# Xibeca.net
KiCad netlist of a schematic drawn in EAGLE
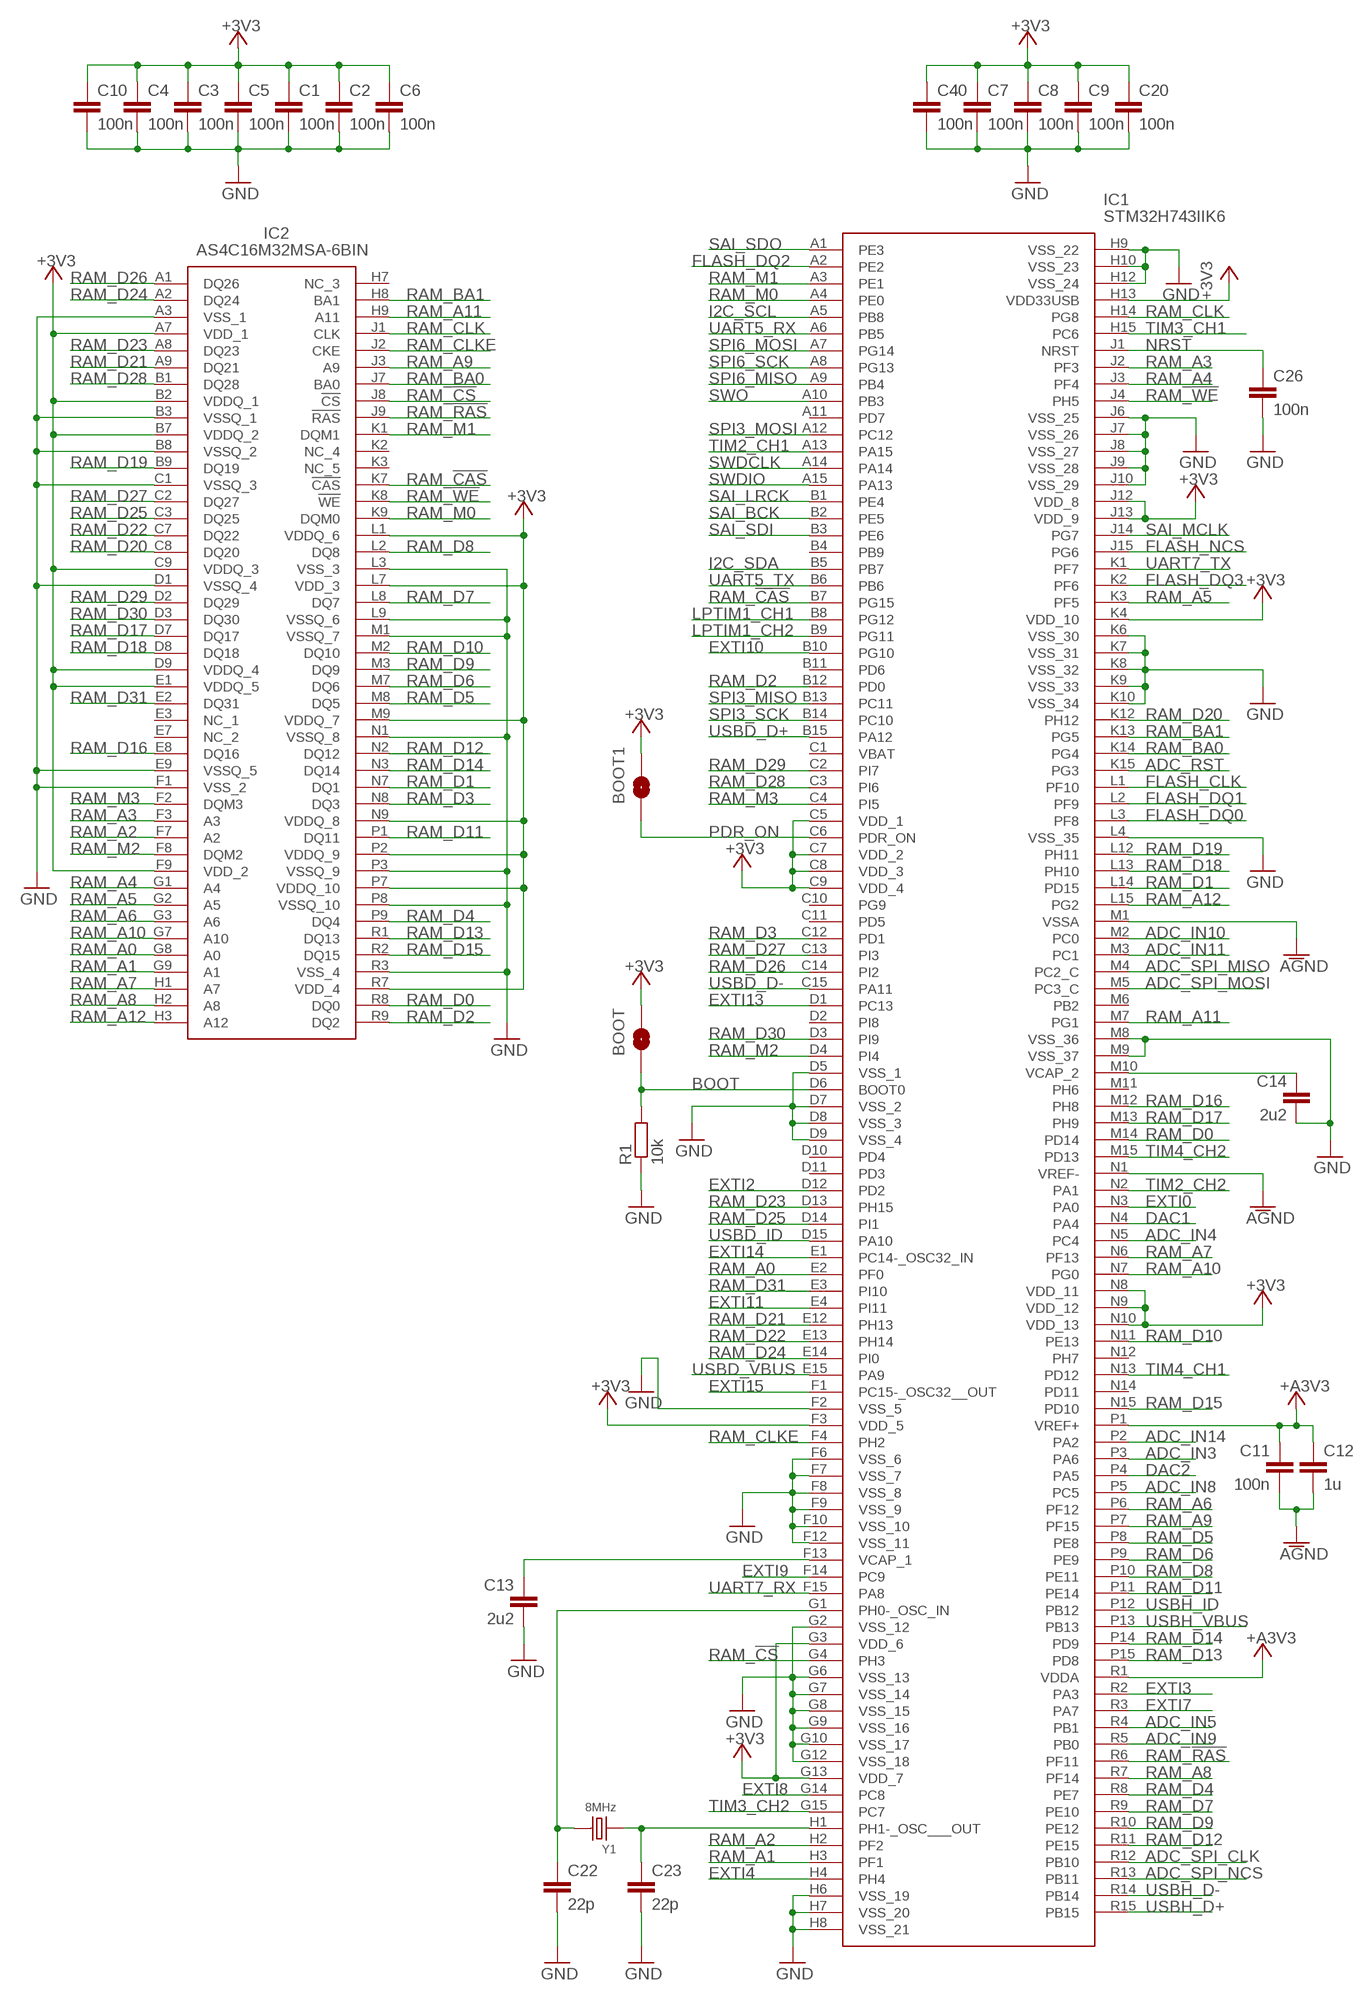
[diagram p0: schematic, sheet 1, part 1 of 2]
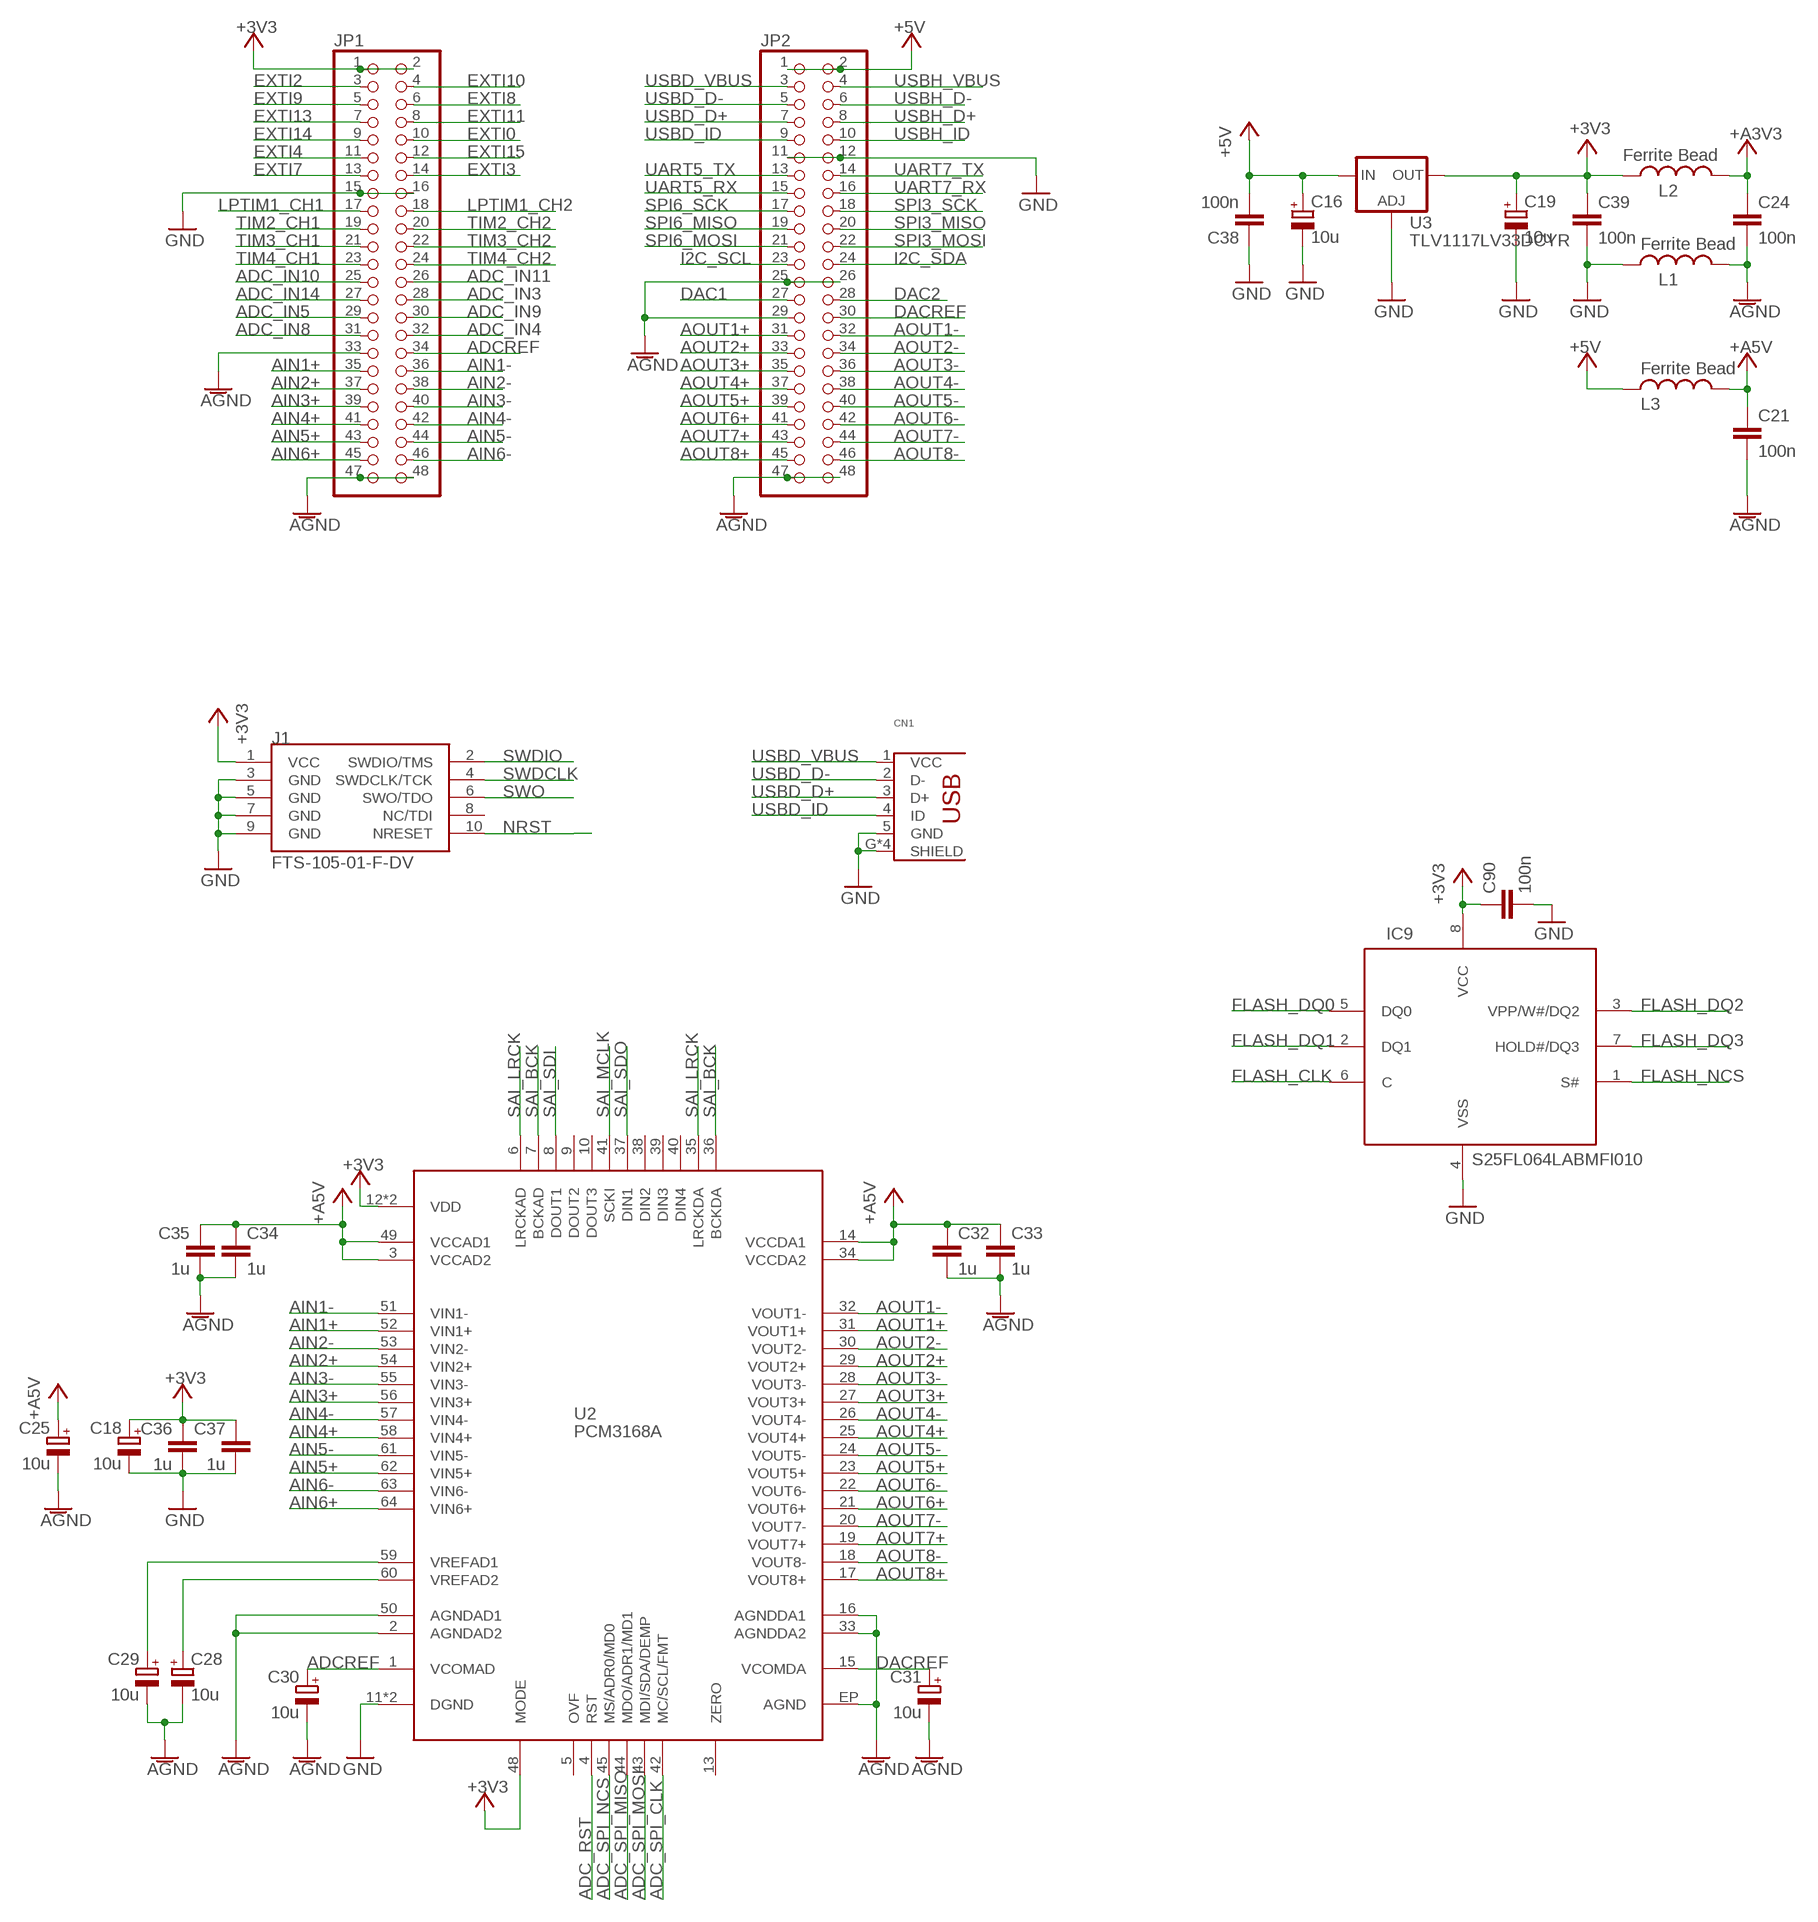
[diagram p1: schematic, sheet 1, part 2 of 2]

(export (version "E")
  (design (tool "Eeschema 10.0.6"))
  (components
    (comp (ref "BOOT")
      (value "SOLDERJUMPERNO")
      (footprint "eagle-import:SJ_2S-NO")
      (libsource (lib "eagle-import") (part "SOLDERJUMPERNO"))
    )
    (comp (ref "BOOT1")
      (value "SOLDERJUMPERNO")
      (footprint "eagle-import:SJ_2S-NO")
      (libsource (lib "eagle-import") (part "SOLDERJUMPERNO"))
    )
    (comp (ref "C1")
      (value "100n")
      (footprint "eagle-import:C0402")
      (libsource (lib "eagle-import") (part "C-EUC0402"))
    )
    (comp (ref "C2")
      (value "100n")
      (footprint "eagle-import:C0402")
      (libsource (lib "eagle-import") (part "C-EUC0402"))
    )
    (comp (ref "C3")
      (value "100n")
      (footprint "eagle-import:C0402")
      (libsource (lib "eagle-import") (part "C-EUC0402"))
    )
    (comp (ref "C4")
      (value "100n")
      (footprint "eagle-import:C0402")
      (libsource (lib "eagle-import") (part "C-EUC0402"))
    )
    (comp (ref "C5")
      (value "100n")
      (footprint "eagle-import:C0402")
      (libsource (lib "eagle-import") (part "C-EUC0402"))
    )
    (comp (ref "C6")
      (value "100n")
      (footprint "eagle-import:C0402")
      (libsource (lib "eagle-import") (part "C-EUC0402"))
    )
    (comp (ref "C7")
      (value "100n")
      (footprint "eagle-import:C0402")
      (libsource (lib "eagle-import") (part "C-EUC0402"))
    )
    (comp (ref "C8")
      (value "100n")
      (footprint "eagle-import:C0402")
      (libsource (lib "eagle-import") (part "C-EUC0402"))
    )
    (comp (ref "C9")
      (value "100n")
      (footprint "eagle-import:C0402")
      (libsource (lib "eagle-import") (part "C-EUC0402"))
    )
    (comp (ref "C10")
      (value "100n")
      (footprint "eagle-import:C0402")
      (libsource (lib "eagle-import") (part "C-EUC0402"))
    )
    (comp (ref "C11")
      (value "100n")
      (footprint "eagle-import:C0402")
      (libsource (lib "eagle-import") (part "C-EUC0402"))
    )
    (comp (ref "C12")
      (value "1u")
      (footprint "eagle-import:C0603")
      (libsource (lib "eagle-import") (part "C-EUC0603"))
    )
    (comp (ref "C13")
      (value "2u2")
      (footprint "eagle-import:C0402")
      (libsource (lib "eagle-import") (part "C-EUC0402"))
    )
    (comp (ref "C14")
      (value "2u2")
      (footprint "eagle-import:C0402")
      (libsource (lib "eagle-import") (part "C-EUC0402"))
    )
    (comp (ref "C16")
      (value "10u")
      (footprint "eagle-import:UD-4X5,8_NICHICON")
      (libsource (lib "eagle-import") (part "CPOL-EUUD-4X5,8"))
    )
    (comp (ref "C18")
      (value "10u")
      (footprint "eagle-import:UD-4X5,8_NICHICON")
      (libsource (lib "eagle-import") (part "CPOL-EUUD-4X5,8"))
    )
    (comp (ref "C19")
      (value "10u")
      (footprint "eagle-import:UD-4X5,8_NICHICON")
      (libsource (lib "eagle-import") (part "CPOL-EUUD-4X5,8"))
    )
    (comp (ref "C20")
      (value "100n")
      (footprint "eagle-import:C0402")
      (libsource (lib "eagle-import") (part "C-EUC0402"))
    )
    (comp (ref "C21")
      (value "100n")
      (footprint "eagle-import:C0402")
      (libsource (lib "eagle-import") (part "C-EUC0402"))
    )
    (comp (ref "C22")
      (value "22p")
      (footprint "eagle-import:C0402")
      (libsource (lib "eagle-import") (part "C-EUC0402"))
    )
    (comp (ref "C23")
      (value "22p")
      (footprint "eagle-import:C0402")
      (libsource (lib "eagle-import") (part "C-EUC0402"))
    )
    (comp (ref "C24")
      (value "100n")
      (footprint "eagle-import:C0402")
      (libsource (lib "eagle-import") (part "C-EUC0402"))
    )
    (comp (ref "C25")
      (value "10u")
      (footprint "eagle-import:UD-4X5,8_NICHICON")
      (libsource (lib "eagle-import") (part "CPOL-EUUD-4X5,8"))
    )
    (comp (ref "C26")
      (value "100n")
      (footprint "eagle-import:C0402")
      (libsource (lib "eagle-import") (part "C-EUC0402"))
    )
    (comp (ref "C28")
      (value "10u")
      (footprint "eagle-import:UD-4X5,8_NICHICON")
      (libsource (lib "eagle-import") (part "CPOL-EUUD-4X5,8"))
    )
    (comp (ref "C29")
      (value "10u")
      (footprint "eagle-import:UD-4X5,8_NICHICON")
      (libsource (lib "eagle-import") (part "CPOL-EUUD-4X5,8"))
    )
    (comp (ref "C30")
      (value "10u")
      (footprint "eagle-import:UD-4X5,8_NICHICON")
      (libsource (lib "eagle-import") (part "CPOL-EUUD-4X5,8"))
    )
    (comp (ref "C31")
      (value "10u")
      (footprint "eagle-import:UD-4X5,8_NICHICON")
      (libsource (lib "eagle-import") (part "CPOL-EUUD-4X5,8"))
    )
    (comp (ref "C32")
      (value "1u")
      (footprint "eagle-import:C0603")
      (libsource (lib "eagle-import") (part "C-EUC0603"))
    )
    (comp (ref "C33")
      (value "1u")
      (footprint "eagle-import:C0603")
      (libsource (lib "eagle-import") (part "C-EUC0603"))
    )
    (comp (ref "C34")
      (value "1u")
      (footprint "eagle-import:C0603")
      (libsource (lib "eagle-import") (part "C-EUC0603"))
    )
    (comp (ref "C35")
      (value "1u")
      (footprint "eagle-import:C0603")
      (libsource (lib "eagle-import") (part "C-EUC0603"))
    )
    (comp (ref "C36")
      (value "1u")
      (footprint "eagle-import:C0603")
      (libsource (lib "eagle-import") (part "C-EUC0603"))
    )
    (comp (ref "C37")
      (value "1u")
      (footprint "eagle-import:C0603")
      (libsource (lib "eagle-import") (part "C-EUC0603"))
    )
    (comp (ref "C38")
      (value "100n")
      (footprint "eagle-import:C0402")
      (libsource (lib "eagle-import") (part "C-EUC0402"))
    )
    (comp (ref "C39")
      (value "100n")
      (footprint "eagle-import:C0402")
      (libsource (lib "eagle-import") (part "C-EUC0402"))
    )
    (comp (ref "C40")
      (value "100n")
      (footprint "eagle-import:C0402")
      (libsource (lib "eagle-import") (part "C-EUC0402"))
    )
    (comp (ref "C90")
      (value "100n")
      (footprint "eagle-import:C0402")
      (libsource (lib "eagle-import") (part "C-EUC0402"))
    )
    (comp (ref "CN1")
      (value "USB_HRS_ZX62-B-5PA(11)MICRO.B")
      (footprint "eagle-import:HRS_ZX62RD-AB-5P8")
      (libsource (lib "eagle-import") (part "USB_HRS_ZX62-B-5PA(11)MICRO.B"))
    )
    (comp (ref "IC1")
      (value "STM32H743IIK6")
      (footprint "eagle-import:BGA201C65P15X15_1000X1000X60")
      (fields (field (name "MOUSER_PART_NUMBER") "511-STM32H743IIK6"))
      (libsource (lib "eagle-import") (part "STM32H743IIK6"))
    )
    (comp (ref "IC2")
      (value "AS4C16M32MSA-6BIN")
      (footprint "eagle-import:BGA90C80P9X15_800X1300X100")
      (fields (field (name "MOUSER_PART_NUMBER") "913-AS4C16M32MSA6BIN"))
      (libsource (lib "eagle-import") (part "AS4C16M32MSA-6BIN"))
    )
    (comp (ref "IC9")
      (value "S25FL064LABMFI010")
      (footprint "eagle-import:SO8W")
      (libsource (lib "eagle-import") (part "N25Q128A13"))
    )
    (comp (ref "J1")
      (value "FTS-105-01-F-DV")
      (footprint "eagle-import:2X5_1.27MM_SMD")
      (libsource (lib "eagle-import") (part "ARM_10SMD"))
    )
    (comp (ref "JP1")
      (value "PINHD-2X24")
      (footprint "eagle-import:2X24")
      (libsource (lib "eagle-import") (part "PINHD-2X24"))
    )
    (comp (ref "JP2")
      (value "PINHD-2X24")
      (footprint "eagle-import:2X24")
      (libsource (lib "eagle-import") (part "PINHD-2X24"))
    )
    (comp (ref "L1")
      (value "Ferrite Bead")
      (footprint "eagle-import:0603")
      (libsource (lib "eagle-import") (part "INDUCTOR"))
    )
    (comp (ref "L2")
      (value "Ferrite Bead")
      (footprint "eagle-import:0603")
      (libsource (lib "eagle-import") (part "INDUCTOR"))
    )
    (comp (ref "L3")
      (value "Ferrite Bead")
      (footprint "eagle-import:0603")
      (libsource (lib "eagle-import") (part "INDUCTOR"))
    )
    (comp (ref "R1")
      (value "10k")
      (footprint "eagle-import:0603")
      (libsource (lib "eagle-import") (part "R-EU_0603"))
    )
    (comp (ref "U2")
      (value "PCM3168A")
      (footprint "eagle-import:PQFP64")
      (libsource (lib "eagle-import") (part "PCM3168A"))
    )
    (comp (ref "U3")
      (value "TLV1117LV33DCYR")
      (footprint "eagle-import:SOT223")
      (libsource (lib "eagle-import") (part "LD117A?S33TR"))
    )
    (comp (ref "Y1")
      (value "8MHz")
      (footprint "eagle-import:X2-SMD-5.0X3.2X1.3MM")
      (fields (field (name "MPN") "5032/2P"))
      (libsource (lib "eagle-import") (part "SMD-CRYSTAL-8MHZ-20PF-20PPM(2P-5.0X3.2MM)"))
    )
  )
  (nets
    (net (code "1") (name "+3V3") (class "Default")
      (node (ref "BOOT") (pin "1") (pinfunction "1_1") (pintype "passive"))
      (node (ref "BOOT1") (pin "1") (pinfunction "1_1") (pintype "passive"))
      (node (ref "C1") (pin "1") (pinfunction "1_1") (pintype "passive"))
      (node (ref "C10") (pin "1") (pinfunction "1_1") (pintype "passive"))
      (node (ref "C18") (pin "+") (pinfunction "+_+") (pintype "passive"))
      (node (ref "C19") (pin "+") (pinfunction "+_+") (pintype "passive"))
      (node (ref "C2") (pin "1") (pinfunction "1_1") (pintype "passive"))
      (node (ref "C20") (pin "1") (pinfunction "1_1") (pintype "passive"))
      (node (ref "C3") (pin "1") (pinfunction "1_1") (pintype "passive"))
      (node (ref "C36") (pin "1") (pinfunction "1_1") (pintype "passive"))
      (node (ref "C37") (pin "1") (pinfunction "1_1") (pintype "passive"))
      (node (ref "C39") (pin "1") (pinfunction "1_1") (pintype "passive"))
      (node (ref "C4") (pin "1") (pinfunction "1_1") (pintype "passive"))
      (node (ref "C40") (pin "1") (pinfunction "1_1") (pintype "passive"))
      (node (ref "C5") (pin "1") (pinfunction "1_1") (pintype "passive"))
      (node (ref "C6") (pin "1") (pinfunction "1_1") (pintype "passive"))
      (node (ref "C7") (pin "1") (pinfunction "1_1") (pintype "passive"))
      (node (ref "C8") (pin "1") (pinfunction "1_1") (pintype "passive"))
      (node (ref "C9") (pin "1") (pinfunction "1_1") (pintype "passive"))
      (node (ref "C90") (pin "1") (pinfunction "1_1") (pintype "passive"))
      (node (ref "IC1") (pin "C5") (pinfunction "VDD_1_C5") (pintype "bidirectional"))
      (node (ref "IC1") (pin "C7") (pinfunction "VDD_2_C7") (pintype "bidirectional"))
      (node (ref "IC1") (pin "C8") (pinfunction "VDD_3_C8") (pintype "bidirectional"))
      (node (ref "IC1") (pin "C9") (pinfunction "VDD_4_C9") (pintype "bidirectional"))
      (node (ref "IC1") (pin "F3") (pinfunction "VDD_5_F3") (pintype "bidirectional"))
      (node (ref "IC1") (pin "G13") (pinfunction "VDD_7_G13") (pintype "bidirectional"))
      (node (ref "IC1") (pin "G3") (pinfunction "VDD_6_G3") (pintype "bidirectional"))
      (node (ref "IC1") (pin "H13") (pinfunction "VDD33USB_H13") (pintype "bidirectional"))
      (node (ref "IC1") (pin "J12") (pinfunction "VDD_8_J12") (pintype "bidirectional"))
      (node (ref "IC1") (pin "J13") (pinfunction "VDD_9_J13") (pintype "bidirectional"))
      (node (ref "IC1") (pin "K4") (pinfunction "VDD_10_K4") (pintype "bidirectional"))
      (node (ref "IC1") (pin "N10") (pinfunction "VDD_13_N10") (pintype "bidirectional"))
      (node (ref "IC1") (pin "N8") (pinfunction "VDD_11_N8") (pintype "bidirectional"))
      (node (ref "IC1") (pin "N9") (pinfunction "VDD_12_N9") (pintype "bidirectional"))
      (node (ref "IC2") (pin "A7") (pinfunction "VDD_1_A7") (pintype "bidirectional"))
      (node (ref "IC2") (pin "B2") (pinfunction "VDDQ_1_B2") (pintype "bidirectional"))
      (node (ref "IC2") (pin "B7") (pinfunction "VDDQ_2_B7") (pintype "bidirectional"))
      (node (ref "IC2") (pin "C9") (pinfunction "VDDQ_3_C9") (pintype "bidirectional"))
      (node (ref "IC2") (pin "D9") (pinfunction "VDDQ_4_D9") (pintype "bidirectional"))
      (node (ref "IC2") (pin "E1") (pinfunction "VDDQ_5_E1") (pintype "bidirectional"))
      (node (ref "IC2") (pin "F9") (pinfunction "VDD_2_F9") (pintype "bidirectional"))
      (node (ref "IC2") (pin "L1") (pinfunction "VDDQ_6_L1") (pintype "bidirectional"))
      (node (ref "IC2") (pin "L7") (pinfunction "VDD_3_L7") (pintype "bidirectional"))
      (node (ref "IC2") (pin "M9") (pinfunction "VDDQ_7_M9") (pintype "bidirectional"))
      (node (ref "IC2") (pin "N9") (pinfunction "VDDQ_8_N9") (pintype "bidirectional"))
      (node (ref "IC2") (pin "P2") (pinfunction "VDDQ_9_P2") (pintype "bidirectional"))
      (node (ref "IC2") (pin "P7") (pinfunction "VDDQ_10_P7") (pintype "bidirectional"))
      (node (ref "IC2") (pin "R7") (pinfunction "VDD_4_R7") (pintype "bidirectional"))
      (node (ref "IC9") (pin "8") (pinfunction "VCC_8") (pintype "bidirectional"))
      (node (ref "J1") (pin "1") (pinfunction "VCC_1") (pintype "bidirectional"))
      (node (ref "JP1") (pin "1") (pinfunction "1_1") (pintype "passive"))
      (node (ref "JP1") (pin "2") (pinfunction "2_2") (pintype "passive"))
      (node (ref "L2") (pin "2") (pinfunction "2_2") (pintype "passive"))
      (node (ref "U2") (pin "12") (pinfunction "VDD_12") (pintype "bidirectional"))
      (node (ref "U2") (pin "46") (pinfunction "VDD_46") (pintype "bidirectional"))
      (node (ref "U2") (pin "48") (pinfunction "MODE_48") (pintype "bidirectional"))
      (node (ref "U3") (pin "4") (pinfunction "OUT_4") (pintype "passive"))
    )
    (net (code "2") (name "+5V") (class "Default")
      (node (ref "C16") (pin "+") (pinfunction "+_+") (pintype "passive"))
      (node (ref "C38") (pin "2") (pinfunction "2_2") (pintype "passive"))
      (node (ref "JP2") (pin "1") (pinfunction "1_1") (pintype "passive"))
      (node (ref "JP2") (pin "2") (pinfunction "2_2") (pintype "passive"))
      (node (ref "L3") (pin "2") (pinfunction "2_2") (pintype "passive"))
      (node (ref "U3") (pin "3") (pinfunction "IN_3") (pintype "input"))
    )
    (net (code "3") (name "+A3V3") (class "Default")
      (node (ref "C11") (pin "1") (pinfunction "1_1") (pintype "passive"))
      (node (ref "C12") (pin "1") (pinfunction "1_1") (pintype "passive"))
      (node (ref "C24") (pin "1") (pinfunction "1_1") (pintype "passive"))
      (node (ref "IC1") (pin "P1") (pinfunction "VREF+_P1") (pintype "bidirectional"))
      (node (ref "IC1") (pin "R1") (pinfunction "VDDA_R1") (pintype "bidirectional"))
      (node (ref "L2") (pin "1") (pinfunction "1_1") (pintype "passive"))
    )
    (net (code "4") (name "+A5V") (class "Default")
      (node (ref "C21") (pin "1") (pinfunction "1_1") (pintype "passive"))
      (node (ref "C25") (pin "+") (pinfunction "+_+") (pintype "passive"))
      (node (ref "C32") (pin "1") (pinfunction "1_1") (pintype "passive"))
      (node (ref "C33") (pin "1") (pinfunction "1_1") (pintype "passive"))
      (node (ref "C34") (pin "1") (pinfunction "1_1") (pintype "passive"))
      (node (ref "C35") (pin "1") (pinfunction "1_1") (pintype "passive"))
      (node (ref "L3") (pin "1") (pinfunction "1_1") (pintype "passive"))
      (node (ref "U2") (pin "14") (pinfunction "VCCDA1_14") (pintype "bidirectional"))
      (node (ref "U2") (pin "3") (pinfunction "VCCAD2_3") (pintype "bidirectional"))
      (node (ref "U2") (pin "34") (pinfunction "VCCDA2_34") (pintype "bidirectional"))
      (node (ref "U2") (pin "49") (pinfunction "VCCAD1_49") (pintype "bidirectional"))
    )
    (net (code "5") (name "/ADCREF") (class "Default")
      (node (ref "C30") (pin "+") (pinfunction "+_+") (pintype "passive"))
      (node (ref "JP1") (pin "34") (pinfunction "34_34") (pintype "passive"))
      (node (ref "U2") (pin "1") (pinfunction "VCOMAD_1") (pintype "bidirectional"))
    )
    (net (code "6") (name "/ADC_IN3") (class "Default")
      (node (ref "IC1") (pin "P3") (pinfunction "PA6_P3") (pintype "bidirectional"))
      (node (ref "JP1") (pin "28") (pinfunction "28_28") (pintype "passive"))
    )
    (net (code "7") (name "/ADC_IN4") (class "Default")
      (node (ref "IC1") (pin "N5") (pinfunction "PC4_N5") (pintype "bidirectional"))
      (node (ref "JP1") (pin "32") (pinfunction "32_32") (pintype "passive"))
    )
    (net (code "8") (name "/ADC_IN5") (class "Default")
      (node (ref "IC1") (pin "R4") (pinfunction "PB1_R4") (pintype "bidirectional"))
      (node (ref "JP1") (pin "29") (pinfunction "29_29") (pintype "passive"))
    )
    (net (code "9") (name "/ADC_IN8") (class "Default")
      (node (ref "IC1") (pin "P5") (pinfunction "PC5_P5") (pintype "bidirectional"))
      (node (ref "JP1") (pin "31") (pinfunction "31_31") (pintype "passive"))
    )
    (net (code "10") (name "/ADC_IN9") (class "Default")
      (node (ref "IC1") (pin "R5") (pinfunction "PB0_R5") (pintype "bidirectional"))
      (node (ref "JP1") (pin "30") (pinfunction "30_30") (pintype "passive"))
    )
    (net (code "11") (name "/ADC_IN10") (class "Default")
      (node (ref "IC1") (pin "M2") (pinfunction "PC0_M2") (pintype "bidirectional"))
      (node (ref "JP1") (pin "25") (pinfunction "25_25") (pintype "passive"))
    )
    (net (code "12") (name "/ADC_IN11") (class "Default")
      (node (ref "IC1") (pin "M3") (pinfunction "PC1_M3") (pintype "bidirectional"))
      (node (ref "JP1") (pin "26") (pinfunction "26_26") (pintype "passive"))
    )
    (net (code "13") (name "/ADC_IN14") (class "Default")
      (node (ref "IC1") (pin "P2") (pinfunction "PA2_P2") (pintype "bidirectional"))
      (node (ref "JP1") (pin "27") (pinfunction "27_27") (pintype "passive"))
    )
    (net (code "14") (name "/ADC_RST") (class "Default")
      (node (ref "IC1") (pin "K15") (pinfunction "PG3_K15") (pintype "bidirectional"))
      (node (ref "U2") (pin "4") (pinfunction "RST_4") (pintype "bidirectional"))
    )
    (net (code "15") (name "/ADC_SPI_CLK") (class "Default")
      (node (ref "IC1") (pin "R12") (pinfunction "PB10_R12") (pintype "bidirectional"))
      (node (ref "U2") (pin "42") (pinfunction "MC/SCL/FMT_42") (pintype "bidirectional"))
    )
    (net (code "16") (name "/ADC_SPI_MISO") (class "Default")
      (node (ref "IC1") (pin "M4") (pinfunction "PC2_C_M4") (pintype "bidirectional"))
      (node (ref "U2") (pin "44") (pinfunction "MDO/ADR1/MD1_44") (pintype "bidirectional"))
    )
    (net (code "17") (name "/ADC_SPI_MOSI") (class "Default")
      (node (ref "IC1") (pin "M5") (pinfunction "PC3_C_M5") (pintype "bidirectional"))
      (node (ref "U2") (pin "43") (pinfunction "MDI/SDA/DEMP_43") (pintype "bidirectional"))
    )
    (net (code "18") (name "/ADC_SPI_NCS") (class "Default")
      (node (ref "IC1") (pin "R13") (pinfunction "PB11_R13") (pintype "bidirectional"))
      (node (ref "U2") (pin "45") (pinfunction "MS/ADR0/MD0_45") (pintype "bidirectional"))
    )
    (net (code "19") (name "/AIN1+") (class "Default")
      (node (ref "JP1") (pin "35") (pinfunction "35_35") (pintype "passive"))
      (node (ref "U2") (pin "52") (pinfunction "VIN1+_52") (pintype "bidirectional"))
    )
    (net (code "20") (name "/AIN1-") (class "Default")
      (node (ref "JP1") (pin "36") (pinfunction "36_36") (pintype "passive"))
      (node (ref "U2") (pin "51") (pinfunction "VIN1-_51") (pintype "bidirectional"))
    )
    (net (code "21") (name "/AIN2+") (class "Default")
      (node (ref "JP1") (pin "37") (pinfunction "37_37") (pintype "passive"))
      (node (ref "U2") (pin "54") (pinfunction "VIN2+_54") (pintype "bidirectional"))
    )
    (net (code "22") (name "/AIN2-") (class "Default")
      (node (ref "JP1") (pin "38") (pinfunction "38_38") (pintype "passive"))
      (node (ref "U2") (pin "53") (pinfunction "VIN2-_53") (pintype "bidirectional"))
    )
    (net (code "23") (name "/AIN3+") (class "Default")
      (node (ref "JP1") (pin "39") (pinfunction "39_39") (pintype "passive"))
      (node (ref "U2") (pin "56") (pinfunction "VIN3+_56") (pintype "bidirectional"))
    )
    (net (code "24") (name "/AIN3-") (class "Default")
      (node (ref "JP1") (pin "40") (pinfunction "40_40") (pintype "passive"))
      (node (ref "U2") (pin "55") (pinfunction "VIN3-_55") (pintype "bidirectional"))
    )
    (net (code "25") (name "/AIN4+") (class "Default")
      (node (ref "JP1") (pin "41") (pinfunction "41_41") (pintype "passive"))
      (node (ref "U2") (pin "58") (pinfunction "VIN4+_58") (pintype "bidirectional"))
    )
    (net (code "26") (name "/AIN4-") (class "Default")
      (node (ref "JP1") (pin "42") (pinfunction "42_42") (pintype "passive"))
      (node (ref "U2") (pin "57") (pinfunction "VIN4-_57") (pintype "bidirectional"))
    )
    (net (code "27") (name "/AIN5+") (class "Default")
      (node (ref "JP1") (pin "43") (pinfunction "43_43") (pintype "passive"))
      (node (ref "U2") (pin "62") (pinfunction "VIN5+_62") (pintype "bidirectional"))
    )
    (net (code "28") (name "/AIN5-") (class "Default")
      (node (ref "JP1") (pin "44") (pinfunction "44_44") (pintype "passive"))
      (node (ref "U2") (pin "61") (pinfunction "VIN5-_61") (pintype "bidirectional"))
    )
    (net (code "29") (name "/AIN6+") (class "Default")
      (node (ref "JP1") (pin "45") (pinfunction "45_45") (pintype "passive"))
      (node (ref "U2") (pin "64") (pinfunction "VIN6+_64") (pintype "bidirectional"))
    )
    (net (code "30") (name "/AIN6-") (class "Default")
      (node (ref "JP1") (pin "46") (pinfunction "46_46") (pintype "passive"))
      (node (ref "U2") (pin "63") (pinfunction "VIN6-_63") (pintype "bidirectional"))
    )
    (net (code "31") (name "/AOUT1+") (class "Default")
      (node (ref "JP2") (pin "31") (pinfunction "31_31") (pintype "passive"))
      (node (ref "U2") (pin "31") (pinfunction "VOUT1+_31") (pintype "bidirectional"))
    )
    (net (code "32") (name "/AOUT1-") (class "Default")
      (node (ref "JP2") (pin "32") (pinfunction "32_32") (pintype "passive"))
      (node (ref "U2") (pin "32") (pinfunction "VOUT1-_32") (pintype "bidirectional"))
    )
    (net (code "33") (name "/AOUT2+") (class "Default")
      (node (ref "JP2") (pin "33") (pinfunction "33_33") (pintype "passive"))
      (node (ref "U2") (pin "29") (pinfunction "VOUT2+_29") (pintype "bidirectional"))
    )
    (net (code "34") (name "/AOUT2-") (class "Default")
      (node (ref "JP2") (pin "34") (pinfunction "34_34") (pintype "passive"))
      (node (ref "U2") (pin "30") (pinfunction "VOUT2-_30") (pintype "bidirectional"))
    )
    (net (code "35") (name "/AOUT3+") (class "Default")
      (node (ref "JP2") (pin "35") (pinfunction "35_35") (pintype "passive"))
      (node (ref "U2") (pin "27") (pinfunction "VOUT3+_27") (pintype "bidirectional"))
    )
    (net (code "36") (name "/AOUT3-") (class "Default")
      (node (ref "JP2") (pin "36") (pinfunction "36_36") (pintype "passive"))
      (node (ref "U2") (pin "28") (pinfunction "VOUT3-_28") (pintype "bidirectional"))
    )
    (net (code "37") (name "/AOUT4+") (class "Default")
      (node (ref "JP2") (pin "37") (pinfunction "37_37") (pintype "passive"))
      (node (ref "U2") (pin "25") (pinfunction "VOUT4+_25") (pintype "bidirectional"))
    )
    (net (code "38") (name "/AOUT4-") (class "Default")
      (node (ref "JP2") (pin "38") (pinfunction "38_38") (pintype "passive"))
      (node (ref "U2") (pin "26") (pinfunction "VOUT4-_26") (pintype "bidirectional"))
    )
    (net (code "39") (name "/AOUT5+") (class "Default")
      (node (ref "JP2") (pin "39") (pinfunction "39_39") (pintype "passive"))
      (node (ref "U2") (pin "23") (pinfunction "VOUT5+_23") (pintype "bidirectional"))
    )
    (net (code "40") (name "/AOUT5-") (class "Default")
      (node (ref "JP2") (pin "40") (pinfunction "40_40") (pintype "passive"))
      (node (ref "U2") (pin "24") (pinfunction "VOUT5-_24") (pintype "bidirectional"))
    )
    (net (code "41") (name "/AOUT6+") (class "Default")
      (node (ref "JP2") (pin "41") (pinfunction "41_41") (pintype "passive"))
      (node (ref "U2") (pin "21") (pinfunction "VOUT6+_21") (pintype "bidirectional"))
    )
    (net (code "42") (name "/AOUT6-") (class "Default")
      (node (ref "JP2") (pin "42") (pinfunction "42_42") (pintype "passive"))
      (node (ref "U2") (pin "22") (pinfunction "VOUT6-_22") (pintype "bidirectional"))
    )
    (net (code "43") (name "/AOUT7+") (class "Default")
      (node (ref "JP2") (pin "43") (pinfunction "43_43") (pintype "passive"))
      (node (ref "U2") (pin "19") (pinfunction "VOUT7+_19") (pintype "bidirectional"))
    )
    (net (code "44") (name "/AOUT7-") (class "Default")
      (node (ref "JP2") (pin "44") (pinfunction "44_44") (pintype "passive"))
      (node (ref "U2") (pin "20") (pinfunction "VOUT7-_20") (pintype "bidirectional"))
    )
    (net (code "45") (name "/AOUT8+") (class "Default")
      (node (ref "JP2") (pin "45") (pinfunction "45_45") (pintype "passive"))
      (node (ref "U2") (pin "17") (pinfunction "VOUT8+_17") (pintype "bidirectional"))
    )
    (net (code "46") (name "/AOUT8-") (class "Default")
      (node (ref "JP2") (pin "46") (pinfunction "46_46") (pintype "passive"))
      (node (ref "U2") (pin "18") (pinfunction "VOUT8-_18") (pintype "bidirectional"))
    )
    (net (code "47") (name "/BOOT") (class "Default")
      (node (ref "BOOT") (pin "2") (pinfunction "2_2") (pintype "passive"))
      (node (ref "IC1") (pin "D6") (pinfunction "BOOT0_D6") (pintype "bidirectional"))
      (node (ref "R1") (pin "2") (pinfunction "2_2") (pintype "passive"))
    )
    (net (code "48") (name "/DAC1") (class "Default")
      (node (ref "IC1") (pin "N4") (pinfunction "PA4_N4") (pintype "bidirectional"))
      (node (ref "JP2") (pin "27") (pinfunction "27_27") (pintype "passive"))
    )
    (net (code "49") (name "/DAC2") (class "Default")
      (node (ref "IC1") (pin "P4") (pinfunction "PA5_P4") (pintype "bidirectional"))
      (node (ref "JP2") (pin "28") (pinfunction "28_28") (pintype "passive"))
    )
    (net (code "50") (name "/DACREF") (class "Default")
      (node (ref "C31") (pin "+") (pinfunction "+_+") (pintype "passive"))
      (node (ref "JP2") (pin "30") (pinfunction "30_30") (pintype "passive"))
      (node (ref "U2") (pin "15") (pinfunction "VCOMDA_15") (pintype "bidirectional"))
    )
    (net (code "51") (name "/EXTI0") (class "Default")
      (node (ref "IC1") (pin "N3") (pinfunction "PA0_N3") (pintype "bidirectional"))
      (node (ref "JP1") (pin "10") (pinfunction "10_10") (pintype "passive"))
    )
    (net (code "52") (name "/EXTI2") (class "Default")
      (node (ref "IC1") (pin "D12") (pinfunction "PD2_D12") (pintype "bidirectional"))
      (node (ref "JP1") (pin "3") (pinfunction "3_3") (pintype "passive"))
    )
    (net (code "53") (name "/EXTI3") (class "Default")
      (node (ref "IC1") (pin "R2") (pinfunction "PA3_R2") (pintype "bidirectional"))
      (node (ref "JP1") (pin "14") (pinfunction "14_14") (pintype "passive"))
    )
    (net (code "54") (name "/EXTI4") (class "Default")
      (node (ref "IC1") (pin "H4") (pinfunction "PH4_H4") (pintype "bidirectional"))
      (node (ref "JP1") (pin "11") (pinfunction "11_11") (pintype "passive"))
    )
    (net (code "55") (name "/EXTI7") (class "Default")
      (node (ref "IC1") (pin "R3") (pinfunction "PA7_R3") (pintype "bidirectional"))
      (node (ref "JP1") (pin "13") (pinfunction "13_13") (pintype "passive"))
    )
    (net (code "56") (name "/EXTI8") (class "Default")
      (node (ref "IC1") (pin "G14") (pinfunction "PC8_G14") (pintype "bidirectional"))
      (node (ref "JP1") (pin "6") (pinfunction "6_6") (pintype "passive"))
    )
    (net (code "57") (name "/EXTI9") (class "Default")
      (node (ref "IC1") (pin "F14") (pinfunction "PC9_F14") (pintype "bidirectional"))
      (node (ref "JP1") (pin "5") (pinfunction "5_5") (pintype "passive"))
    )
    (net (code "58") (name "/EXTI10") (class "Default")
      (node (ref "IC1") (pin "B10") (pinfunction "PG10_B10") (pintype "bidirectional"))
      (node (ref "JP1") (pin "4") (pinfunction "4_4") (pintype "passive"))
    )
    (net (code "59") (name "/EXTI11") (class "Default")
      (node (ref "IC1") (pin "E4") (pinfunction "PI11_E4") (pintype "bidirectional"))
      (node (ref "JP1") (pin "8") (pinfunction "8_8") (pintype "passive"))
    )
    (net (code "60") (name "/EXTI13") (class "Default")
      (node (ref "IC1") (pin "D1") (pinfunction "PC13_D1") (pintype "bidirectional"))
      (node (ref "JP1") (pin "7") (pinfunction "7_7") (pintype "passive"))
    )
    (net (code "61") (name "/EXTI14") (class "Default")
      (node (ref "IC1") (pin "E1") (pinfunction "PC14-_OSC32_IN_E1") (pintype "bidirectional"))
      (node (ref "JP1") (pin "9") (pinfunction "9_9") (pintype "passive"))
    )
    (net (code "62") (name "/EXTI15") (class "Default")
      (node (ref "IC1") (pin "F1") (pinfunction "PC15-_OSC32__OUT_F1") (pintype "bidirectional"))
      (node (ref "JP1") (pin "12") (pinfunction "12_12") (pintype "passive"))
    )
    (net (code "63") (name "/FLASH_CLK") (class "Default")
      (node (ref "IC1") (pin "L1") (pinfunction "PF10_L1") (pintype "bidirectional"))
      (node (ref "IC9") (pin "6") (pinfunction "C_6") (pintype "bidirectional"))
    )
    (net (code "64") (name "/FLASH_DQ0") (class "Default")
      (node (ref "IC1") (pin "L3") (pinfunction "PF8_L3") (pintype "bidirectional"))
      (node (ref "IC9") (pin "5") (pinfunction "DQ0_5") (pintype "bidirectional"))
    )
    (net (code "65") (name "/FLASH_DQ1") (class "Default")
      (node (ref "IC1") (pin "L2") (pinfunction "PF9_L2") (pintype "bidirectional"))
      (node (ref "IC9") (pin "2") (pinfunction "DQ1_2") (pintype "bidirectional"))
    )
    (net (code "66") (name "/FLASH_DQ2") (class "Default")
      (node (ref "IC1") (pin "A2") (pinfunction "PE2_A2") (pintype "bidirectional"))
      (node (ref "IC9") (pin "3") (pinfunction "VPP/W#/DQ2_3") (pintype "bidirectional"))
    )
    (net (code "67") (name "/FLASH_DQ3") (class "Default")
      (node (ref "IC1") (pin "K2") (pinfunction "PF6_K2") (pintype "bidirectional"))
      (node (ref "IC9") (pin "7") (pinfunction "HOLD#/DQ3_7") (pintype "bidirectional"))
    )
    (net (code "68") (name "/FLASH_NCS") (class "Default")
      (node (ref "IC1") (pin "J15") (pinfunction "PG6_J15") (pintype "bidirectional"))
      (node (ref "IC9") (pin "1") (pinfunction "S#_1") (pintype "bidirectional"))
    )
    (net (code "69") (name "/I2C_SCL") (class "Default")
      (node (ref "IC1") (pin "A5") (pinfunction "PB8_A5") (pintype "bidirectional"))
      (node (ref "JP2") (pin "23") (pinfunction "23_23") (pintype "passive"))
    )
    (net (code "70") (name "/I2C_SDA") (class "Default")
      (node (ref "IC1") (pin "B5") (pinfunction "PB7_B5") (pintype "bidirectional"))
      (node (ref "JP2") (pin "24") (pinfunction "24_24") (pintype "passive"))
    )
    (net (code "71") (name "/LPTIM1_CH1") (class "Default")
      (node (ref "IC1") (pin "B8") (pinfunction "PG12_B8") (pintype "bidirectional"))
      (node (ref "JP1") (pin "17") (pinfunction "17_17") (pintype "passive"))
    )
    (net (code "72") (name "/LPTIM1_CH2") (class "Default")
      (node (ref "IC1") (pin "B9") (pinfunction "PG11_B9") (pintype "bidirectional"))
      (node (ref "JP1") (pin "18") (pinfunction "18_18") (pintype "passive"))
    )
    (net (code "73") (name "/NRST") (class "Default")
      (node (ref "C26") (pin "1") (pinfunction "1_1") (pintype "passive"))
      (node (ref "IC1") (pin "J1") (pinfunction "NRST_J1") (pintype "bidirectional"))
      (node (ref "J1") (pin "10") (pinfunction "NRESET_10") (pintype "bidirectional"))
    )
    (net (code "74") (name "/PDR_ON") (class "Default")
      (node (ref "BOOT1") (pin "2") (pinfunction "2_2") (pintype "passive"))
      (node (ref "IC1") (pin "C6") (pinfunction "PDR_ON_C6") (pintype "bidirectional"))
    )
    (net (code "75") (name "/RAM_A0") (class "Default")
      (node (ref "IC1") (pin "E2") (pinfunction "PF0_E2") (pintype "bidirectional"))
      (node (ref "IC2") (pin "G8") (pinfunction "A0_G8") (pintype "bidirectional"))
    )
    (net (code "76") (name "/RAM_A1") (class "Default")
      (node (ref "IC1") (pin "H3") (pinfunction "PF1_H3") (pintype "bidirectional"))
      (node (ref "IC2") (pin "G9") (pinfunction "A1_G9") (pintype "bidirectional"))
    )
    (net (code "77") (name "/RAM_A2") (class "Default")
      (node (ref "IC1") (pin "H2") (pinfunction "PF2_H2") (pintype "bidirectional"))
      (node (ref "IC2") (pin "F7") (pinfunction "A2_F7") (pintype "bidirectional"))
    )
    (net (code "78") (name "/RAM_A3") (class "Default")
      (node (ref "IC1") (pin "J2") (pinfunction "PF3_J2") (pintype "bidirectional"))
      (node (ref "IC2") (pin "F3") (pinfunction "A3_F3") (pintype "bidirectional"))
    )
    (net (code "79") (name "/RAM_A4") (class "Default")
      (node (ref "IC1") (pin "J3") (pinfunction "PF4_J3") (pintype "bidirectional"))
      (node (ref "IC2") (pin "G1") (pinfunction "A4_G1") (pintype "bidirectional"))
    )
    (net (code "80") (name "/RAM_A5") (class "Default")
      (node (ref "IC1") (pin "K3") (pinfunction "PF5_K3") (pintype "bidirectional"))
      (node (ref "IC2") (pin "G2") (pinfunction "A5_G2") (pintype "bidirectional"))
    )
    (net (code "81") (name "/RAM_A6") (class "Default")
      (node (ref "IC1") (pin "P6") (pinfunction "PF12_P6") (pintype "bidirectional"))
      (node (ref "IC2") (pin "G3") (pinfunction "A6_G3") (pintype "bidirectional"))
    )
    (net (code "82") (name "/RAM_A7") (class "Default")
      (node (ref "IC1") (pin "N6") (pinfunction "PF13_N6") (pintype "bidirectional"))
      (node (ref "IC2") (pin "H1") (pinfunction "A7_H1") (pintype "bidirectional"))
    )
    (net (code "83") (name "/RAM_A8") (class "Default")
      (node (ref "IC1") (pin "R7") (pinfunction "PF14_R7") (pintype "bidirectional"))
      (node (ref "IC2") (pin "H2") (pinfunction "A8_H2") (pintype "bidirectional"))
    )
    (net (code "84") (name "/RAM_A9") (class "Default")
      (node (ref "IC1") (pin "P7") (pinfunction "PF15_P7") (pintype "bidirectional"))
      (node (ref "IC2") (pin "J3") (pinfunction "A9_J3") (pintype "bidirectional"))
    )
    (net (code "85") (name "/RAM_A10") (class "Default")
      (node (ref "IC1") (pin "N7") (pinfunction "PG0_N7") (pintype "bidirectional"))
      (node (ref "IC2") (pin "G7") (pinfunction "A10_G7") (pintype "bidirectional"))
    )
    (net (code "86") (name "/RAM_A11") (class "Default")
      (node (ref "IC1") (pin "M7") (pinfunction "PG1_M7") (pintype "bidirectional"))
      (node (ref "IC2") (pin "H9") (pinfunction "A11_H9") (pintype "bidirectional"))
    )
    (net (code "87") (name "/RAM_A12") (class "Default")
      (node (ref "IC1") (pin "L15") (pinfunction "PG2_L15") (pintype "bidirectional"))
      (node (ref "IC2") (pin "H3") (pinfunction "A12_H3") (pintype "bidirectional"))
    )
    (net (code "88") (name "/RAM_BA0") (class "Default")
      (node (ref "IC1") (pin "K14") (pinfunction "PG4_K14") (pintype "bidirectional"))
      (node (ref "IC2") (pin "J7") (pinfunction "BA0_J7") (pintype "bidirectional"))
    )
    (net (code "89") (name "/RAM_BA1") (class "Default")
      (node (ref "IC1") (pin "K13") (pinfunction "PG5_K13") (pintype "bidirectional"))
      (node (ref "IC2") (pin "H8") (pinfunction "BA1_H8") (pintype "bidirectional"))
    )
    (net (code "90") (name "/RAM_CLK") (class "Default")
      (node (ref "IC1") (pin "H14") (pinfunction "PG8_H14") (pintype "bidirectional"))
      (node (ref "IC2") (pin "J1") (pinfunction "CLK_J1") (pintype "bidirectional"))
    )
    (net (code "91") (name "/RAM_CLKE") (class "Default")
      (node (ref "IC1") (pin "F4") (pinfunction "PH2_F4") (pintype "bidirectional"))
      (node (ref "IC2") (pin "J2") (pinfunction "CKE_J2") (pintype "bidirectional"))
    )
    (net (code "92") (name "/RAM_D0") (class "Default")
      (node (ref "IC1") (pin "M14") (pinfunction "PD14_M14") (pintype "bidirectional"))
      (node (ref "IC2") (pin "R8") (pinfunction "DQ0_R8") (pintype "bidirectional"))
    )
    (net (code "93") (name "/RAM_D1") (class "Default")
      (node (ref "IC1") (pin "L14") (pinfunction "PD15_L14") (pintype "bidirectional"))
      (node (ref "IC2") (pin "N7") (pinfunction "DQ1_N7") (pintype "bidirectional"))
    )
    (net (code "94") (name "/RAM_D2") (class "Default")
      (node (ref "IC1") (pin "B12") (pinfunction "PD0_B12") (pintype "bidirectional"))
      (node (ref "IC2") (pin "R9") (pinfunction "DQ2_R9") (pintype "bidirectional"))
    )
    (net (code "95") (name "/RAM_D3") (class "Default")
      (node (ref "IC1") (pin "C12") (pinfunction "PD1_C12") (pintype "bidirectional"))
      (node (ref "IC2") (pin "N8") (pinfunction "DQ3_N8") (pintype "bidirectional"))
    )
    (net (code "96") (name "/RAM_D4") (class "Default")
      (node (ref "IC1") (pin "R8") (pinfunction "PE7_R8") (pintype "bidirectional"))
      (node (ref "IC2") (pin "P9") (pinfunction "DQ4_P9") (pintype "bidirectional"))
    )
    (net (code "97") (name "/RAM_D5") (class "Default")
      (node (ref "IC1") (pin "P8") (pinfunction "PE8_P8") (pintype "bidirectional"))
      (node (ref "IC2") (pin "M8") (pinfunction "DQ5_M8") (pintype "bidirectional"))
    )
    (net (code "98") (name "/RAM_D6") (class "Default")
      (node (ref "IC1") (pin "P9") (pinfunction "PE9_P9") (pintype "bidirectional"))
      (node (ref "IC2") (pin "M7") (pinfunction "DQ6_M7") (pintype "bidirectional"))
    )
    (net (code "99") (name "/RAM_D7") (class "Default")
      (node (ref "IC1") (pin "R9") (pinfunction "PE10_R9") (pintype "bidirectional"))
      (node (ref "IC2") (pin "L8") (pinfunction "DQ7_L8") (pintype "bidirectional"))
    )
    (net (code "100") (name "/RAM_D8") (class "Default")
      (node (ref "IC1") (pin "P10") (pinfunction "PE11_P10") (pintype "bidirectional"))
      (node (ref "IC2") (pin "L2") (pinfunction "DQ8_L2") (pintype "bidirectional"))
    )
    (net (code "101") (name "/RAM_D9") (class "Default")
      (node (ref "IC1") (pin "R10") (pinfunction "PE12_R10") (pintype "bidirectional"))
      (node (ref "IC2") (pin "M3") (pinfunction "DQ9_M3") (pintype "bidirectional"))
    )
    (net (code "102") (name "/RAM_D10") (class "Default")
      (node (ref "IC1") (pin "N11") (pinfunction "PE13_N11") (pintype "bidirectional"))
      (node (ref "IC2") (pin "M2") (pinfunction "DQ10_M2") (pintype "bidirectional"))
    )
    (net (code "103") (name "/RAM_D11") (class "Default")
      (node (ref "IC1") (pin "P11") (pinfunction "PE14_P11") (pintype "bidirectional"))
      (node (ref "IC2") (pin "P1") (pinfunction "DQ11_P1") (pintype "bidirectional"))
    )
    (net (code "104") (name "/RAM_D12") (class "Default")
      (node (ref "IC1") (pin "R11") (pinfunction "PE15_R11") (pintype "bidirectional"))
      (node (ref "IC2") (pin "N2") (pinfunction "DQ12_N2") (pintype "bidirectional"))
    )
    (net (code "105") (name "/RAM_D13") (class "Default")
      (node (ref "IC1") (pin "P15") (pinfunction "PD8_P15") (pintype "bidirectional"))
      (node (ref "IC2") (pin "R1") (pinfunction "DQ13_R1") (pintype "bidirectional"))
    )
    (net (code "106") (name "/RAM_D14") (class "Default")
      (node (ref "IC1") (pin "P14") (pinfunction "PD9_P14") (pintype "bidirectional"))
      (node (ref "IC2") (pin "N3") (pinfunction "DQ14_N3") (pintype "bidirectional"))
    )
    (net (code "107") (name "/RAM_D15") (class "Default")
      (node (ref "IC1") (pin "N15") (pinfunction "PD10_N15") (pintype "bidirectional"))
      (node (ref "IC2") (pin "R2") (pinfunction "DQ15_R2") (pintype "bidirectional"))
    )
    (net (code "108") (name "/RAM_D16") (class "Default")
      (node (ref "IC1") (pin "M12") (pinfunction "PH8_M12") (pintype "bidirectional"))
      (node (ref "IC2") (pin "E8") (pinfunction "DQ16_E8") (pintype "bidirectional"))
    )
    (net (code "109") (name "/RAM_D17") (class "Default")
      (node (ref "IC1") (pin "M13") (pinfunction "PH9_M13") (pintype "bidirectional"))
      (node (ref "IC2") (pin "D7") (pinfunction "DQ17_D7") (pintype "bidirectional"))
    )
    (net (code "110") (name "/RAM_D18") (class "Default")
      (node (ref "IC1") (pin "L13") (pinfunction "PH10_L13") (pintype "bidirectional"))
      (node (ref "IC2") (pin "D8") (pinfunction "DQ18_D8") (pintype "bidirectional"))
    )
    (net (code "111") (name "/RAM_D19") (class "Default")
      (node (ref "IC1") (pin "L12") (pinfunction "PH11_L12") (pintype "bidirectional"))
      (node (ref "IC2") (pin "B9") (pinfunction "DQ19_B9") (pintype "bidirectional"))
    )
    (net (code "112") (name "/RAM_D20") (class "Default")
      (node (ref "IC1") (pin "K12") (pinfunction "PH12_K12") (pintype "bidirectional"))
      (node (ref "IC2") (pin "C8") (pinfunction "DQ20_C8") (pintype "bidirectional"))
    )
    (net (code "113") (name "/RAM_D21") (class "Default")
      (node (ref "IC1") (pin "E12") (pinfunction "PH13_E12") (pintype "bidirectional"))
      (node (ref "IC2") (pin "A9") (pinfunction "DQ21_A9") (pintype "bidirectional"))
    )
    (net (code "114") (name "/RAM_D22") (class "Default")
      (node (ref "IC1") (pin "E13") (pinfunction "PH14_E13") (pintype "bidirectional"))
      (node (ref "IC2") (pin "C7") (pinfunction "DQ22_C7") (pintype "bidirectional"))
    )
    (net (code "115") (name "/RAM_D23") (class "Default")
      (node (ref "IC1") (pin "D13") (pinfunction "PH15_D13") (pintype "bidirectional"))
      (node (ref "IC2") (pin "A8") (pinfunction "DQ23_A8") (pintype "bidirectional"))
    )
    (net (code "116") (name "/RAM_D24") (class "Default")
      (node (ref "IC1") (pin "E14") (pinfunction "PI0_E14") (pintype "bidirectional"))
      (node (ref "IC2") (pin "A2") (pinfunction "DQ24_A2") (pintype "bidirectional"))
    )
    (net (code "117") (name "/RAM_D25") (class "Default")
      (node (ref "IC1") (pin "D14") (pinfunction "PI1_D14") (pintype "bidirectional"))
      (node (ref "IC2") (pin "C3") (pinfunction "DQ25_C3") (pintype "bidirectional"))
    )
    (net (code "118") (name "/RAM_D26") (class "Default")
      (node (ref "IC1") (pin "C14") (pinfunction "PI2_C14") (pintype "bidirectional"))
      (node (ref "IC2") (pin "A1") (pinfunction "DQ26_A1") (pintype "bidirectional"))
    )
    (net (code "119") (name "/RAM_D27") (class "Default")
      (node (ref "IC1") (pin "C13") (pinfunction "PI3_C13") (pintype "bidirectional"))
      (node (ref "IC2") (pin "C2") (pinfunction "DQ27_C2") (pintype "bidirectional"))
    )
    (net (code "120") (name "/RAM_D28") (class "Default")
      (node (ref "IC1") (pin "C3") (pinfunction "PI6_C3") (pintype "bidirectional"))
      (node (ref "IC2") (pin "B1") (pinfunction "DQ28_B1") (pintype "bidirectional"))
    )
    (net (code "121") (name "/RAM_D29") (class "Default")
      (node (ref "IC1") (pin "C2") (pinfunction "PI7_C2") (pintype "bidirectional"))
      (node (ref "IC2") (pin "D2") (pinfunction "DQ29_D2") (pintype "bidirectional"))
    )
    (net (code "122") (name "/RAM_D30") (class "Default")
      (node (ref "IC1") (pin "D3") (pinfunction "PI9_D3") (pintype "bidirectional"))
      (node (ref "IC2") (pin "D3") (pinfunction "DQ30_D3") (pintype "bidirectional"))
    )
    (net (code "123") (name "/RAM_D31") (class "Default")
      (node (ref "IC1") (pin "E3") (pinfunction "PI10_E3") (pintype "bidirectional"))
      (node (ref "IC2") (pin "E2") (pinfunction "DQ31_E2") (pintype "bidirectional"))
    )
    (net (code "124") (name "/RAM_M0") (class "Default")
      (node (ref "IC1") (pin "A4") (pinfunction "PE0_A4") (pintype "bidirectional"))
      (node (ref "IC2") (pin "K9") (pinfunction "DQM0_K9") (pintype "bidirectional"))
    )
    (net (code "125") (name "/RAM_M1") (class "Default")
      (node (ref "IC1") (pin "A3") (pinfunction "PE1_A3") (pintype "bidirectional"))
      (node (ref "IC2") (pin "K1") (pinfunction "DQM1_K1") (pintype "bidirectional"))
    )
    (net (code "126") (name "/RAM_M2") (class "Default")
      (node (ref "IC1") (pin "D4") (pinfunction "PI4_D4") (pintype "bidirectional"))
      (node (ref "IC2") (pin "F8") (pinfunction "DQM2_F8") (pintype "bidirectional"))
    )
    (net (code "127") (name "/RAM_M3") (class "Default")
      (node (ref "IC1") (pin "C4") (pinfunction "PI5_C4") (pintype "bidirectional"))
      (node (ref "IC2") (pin "F2") (pinfunction "DQM3_F2") (pintype "bidirectional"))
    )
    (net (code "128") (name "/RAM_~{CAS}") (class "Default")
      (node (ref "IC1") (pin "B7") (pinfunction "PG15_B7") (pintype "bidirectional"))
      (node (ref "IC2") (pin "K7") (pinfunction "~{CAS}_K7") (pintype "bidirectional"))
    )
    (net (code "129") (name "/RAM_~{CS}") (class "Default")
      (node (ref "IC1") (pin "G4") (pinfunction "PH3_G4") (pintype "bidirectional"))
      (node (ref "IC2") (pin "J8") (pinfunction "~{CS}_J8") (pintype "bidirectional"))
    )
    (net (code "130") (name "/RAM_~{RAS}") (class "Default")
      (node (ref "IC1") (pin "R6") (pinfunction "PF11_R6") (pintype "bidirectional"))
      (node (ref "IC2") (pin "J9") (pinfunction "~{RAS}_J9") (pintype "bidirectional"))
    )
    (net (code "131") (name "/RAM_~{WE}") (class "Default")
      (node (ref "IC1") (pin "J4") (pinfunction "PH5_J4") (pintype "bidirectional"))
      (node (ref "IC2") (pin "K8") (pinfunction "~{WE}_K8") (pintype "bidirectional"))
    )
    (net (code "132") (name "/SAI_BCK") (class "Default")
      (node (ref "IC1") (pin "B2") (pinfunction "PE5_B2") (pintype "bidirectional"))
      (node (ref "U2") (pin "36") (pinfunction "BCKDA_36") (pintype "bidirectional"))
      (node (ref "U2") (pin "7") (pinfunction "BCKAD_7") (pintype "bidirectional"))
    )
    (net (code "133") (name "/SAI_LRCK") (class "Default")
      (node (ref "IC1") (pin "B1") (pinfunction "PE4_B1") (pintype "bidirectional"))
      (node (ref "U2") (pin "35") (pinfunction "LRCKDA_35") (pintype "bidirectional"))
      (node (ref "U2") (pin "6") (pinfunction "LRCKAD_6") (pintype "bidirectional"))
    )
    (net (code "134") (name "/SAI_MCLK") (class "Default")
      (node (ref "IC1") (pin "J14") (pinfunction "PG7_J14") (pintype "bidirectional"))
      (node (ref "U2") (pin "41") (pinfunction "SCKI_41") (pintype "bidirectional"))
    )
    (net (code "135") (name "/SAI_SDI") (class "Default")
      (node (ref "IC1") (pin "B3") (pinfunction "PE6_B3") (pintype "bidirectional"))
      (node (ref "U2") (pin "8") (pinfunction "DOUT1_8") (pintype "bidirectional"))
    )
    (net (code "136") (name "/SAI_SDO") (class "Default")
      (node (ref "IC1") (pin "A1") (pinfunction "PE3_A1") (pintype "bidirectional"))
      (node (ref "U2") (pin "37") (pinfunction "DIN1_37") (pintype "bidirectional"))
    )
    (net (code "137") (name "/SPI3_MISO") (class "Default")
      (node (ref "IC1") (pin "B13") (pinfunction "PC11_B13") (pintype "bidirectional"))
      (node (ref "JP2") (pin "20") (pinfunction "20_20") (pintype "passive"))
    )
    (net (code "138") (name "/SPI3_MOSI") (class "Default")
      (node (ref "IC1") (pin "A12") (pinfunction "PC12_A12") (pintype "bidirectional"))
      (node (ref "JP2") (pin "22") (pinfunction "22_22") (pintype "passive"))
    )
    (net (code "139") (name "/SPI3_SCK") (class "Default")
      (node (ref "IC1") (pin "B14") (pinfunction "PC10_B14") (pintype "bidirectional"))
      (node (ref "JP2") (pin "18") (pinfunction "18_18") (pintype "passive"))
    )
    (net (code "140") (name "/SPI6_MISO") (class "Default")
      (node (ref "IC1") (pin "A9") (pinfunction "PB4_A9") (pintype "bidirectional"))
      (node (ref "JP2") (pin "19") (pinfunction "19_19") (pintype "passive"))
    )
    (net (code "141") (name "/SPI6_MOSI") (class "Default")
      (node (ref "IC1") (pin "A7") (pinfunction "PG14_A7") (pintype "bidirectional"))
      (node (ref "JP2") (pin "21") (pinfunction "21_21") (pintype "passive"))
    )
    (net (code "142") (name "/SPI6_SCK") (class "Default")
      (node (ref "IC1") (pin "A8") (pinfunction "PG13_A8") (pintype "bidirectional"))
      (node (ref "JP2") (pin "17") (pinfunction "17_17") (pintype "passive"))
    )
    (net (code "143") (name "/SWDCLK") (class "Default")
      (node (ref "IC1") (pin "A14") (pinfunction "PA14_A14") (pintype "bidirectional"))
      (node (ref "J1") (pin "4") (pinfunction "SWDCLK/TCK_4") (pintype "bidirectional"))
    )
    (net (code "144") (name "/SWDIO") (class "Default")
      (node (ref "IC1") (pin "A15") (pinfunction "PA13_A15") (pintype "bidirectional"))
      (node (ref "J1") (pin "2") (pinfunction "SWDIO/TMS_2") (pintype "bidirectional"))
    )
    (net (code "145") (name "/SWO") (class "Default")
      (node (ref "IC1") (pin "A10") (pinfunction "PB3_A10") (pintype "bidirectional"))
      (node (ref "J1") (pin "6") (pinfunction "SWO/TDO_6") (pintype "bidirectional"))
    )
    (net (code "146") (name "/TIM2_CH1") (class "Default")
      (node (ref "IC1") (pin "A13") (pinfunction "PA15_A13") (pintype "bidirectional"))
      (node (ref "JP1") (pin "19") (pinfunction "19_19") (pintype "passive"))
    )
    (net (code "147") (name "/TIM2_CH2") (class "Default")
      (node (ref "IC1") (pin "N2") (pinfunction "PA1_N2") (pintype "bidirectional"))
      (node (ref "JP1") (pin "20") (pinfunction "20_20") (pintype "passive"))
    )
    (net (code "148") (name "/TIM3_CH1") (class "Default")
      (node (ref "IC1") (pin "H15") (pinfunction "PC6_H15") (pintype "bidirectional"))
      (node (ref "JP1") (pin "21") (pinfunction "21_21") (pintype "passive"))
    )
    (net (code "149") (name "/TIM3_CH2") (class "Default")
      (node (ref "IC1") (pin "G15") (pinfunction "PC7_G15") (pintype "bidirectional"))
      (node (ref "JP1") (pin "22") (pinfunction "22_22") (pintype "passive"))
    )
    (net (code "150") (name "/TIM4_CH1") (class "Default")
      (node (ref "IC1") (pin "N13") (pinfunction "PD12_N13") (pintype "bidirectional"))
      (node (ref "JP1") (pin "23") (pinfunction "23_23") (pintype "passive"))
    )
    (net (code "151") (name "/TIM4_CH2") (class "Default")
      (node (ref "IC1") (pin "M15") (pinfunction "PD13_M15") (pintype "bidirectional"))
      (node (ref "JP1") (pin "24") (pinfunction "24_24") (pintype "passive"))
    )
    (net (code "152") (name "/UART5_RX") (class "Default")
      (node (ref "IC1") (pin "A6") (pinfunction "PB5_A6") (pintype "bidirectional"))
      (node (ref "JP2") (pin "15") (pinfunction "15_15") (pintype "passive"))
    )
    (net (code "153") (name "/UART5_TX") (class "Default")
      (node (ref "IC1") (pin "B6") (pinfunction "PB6_B6") (pintype "bidirectional"))
      (node (ref "JP2") (pin "13") (pinfunction "13_13") (pintype "passive"))
    )
    (net (code "154") (name "/UART7_RX") (class "Default")
      (node (ref "IC1") (pin "F15") (pinfunction "PA8_F15") (pintype "bidirectional"))
      (node (ref "JP2") (pin "16") (pinfunction "16_16") (pintype "passive"))
    )
    (net (code "155") (name "/UART7_TX") (class "Default")
      (node (ref "IC1") (pin "K1") (pinfunction "PF7_K1") (pintype "bidirectional"))
      (node (ref "JP2") (pin "14") (pinfunction "14_14") (pintype "passive"))
    )
    (net (code "156") (name "/USBD_D+") (class "Default")
      (node (ref "CN1") (pin "3") (pinfunction "D+_3") (pintype "bidirectional"))
      (node (ref "IC1") (pin "B15") (pinfunction "PA12_B15") (pintype "bidirectional"))
      (node (ref "JP2") (pin "7") (pinfunction "7_7") (pintype "passive"))
    )
    (net (code "157") (name "/USBD_D-") (class "Default")
      (node (ref "CN1") (pin "2") (pinfunction "D-_2") (pintype "bidirectional"))
      (node (ref "IC1") (pin "C15") (pinfunction "PA11_C15") (pintype "bidirectional"))
      (node (ref "JP2") (pin "5") (pinfunction "5_5") (pintype "passive"))
    )
    (net (code "158") (name "/USBD_ID") (class "Default")
      (node (ref "CN1") (pin "4") (pinfunction "ID_4") (pintype "bidirectional"))
      (node (ref "IC1") (pin "D15") (pinfunction "PA10_D15") (pintype "bidirectional"))
      (node (ref "JP2") (pin "9") (pinfunction "9_9") (pintype "passive"))
    )
    (net (code "159") (name "/USBD_VBUS") (class "Default")
      (node (ref "CN1") (pin "1") (pinfunction "VCC_1") (pintype "bidirectional"))
      (node (ref "IC1") (pin "E15") (pinfunction "PA9_E15") (pintype "bidirectional"))
      (node (ref "JP2") (pin "3") (pinfunction "3_3") (pintype "passive"))
    )
    (net (code "160") (name "/USBH_D+") (class "Default")
      (node (ref "IC1") (pin "R15") (pinfunction "PB15_R15") (pintype "bidirectional"))
      (node (ref "JP2") (pin "8") (pinfunction "8_8") (pintype "passive"))
    )
    (net (code "161") (name "/USBH_D-") (class "Default")
      (node (ref "IC1") (pin "R14") (pinfunction "PB14_R14") (pintype "bidirectional"))
      (node (ref "JP2") (pin "6") (pinfunction "6_6") (pintype "passive"))
    )
    (net (code "162") (name "/USBH_ID") (class "Default")
      (node (ref "IC1") (pin "P12") (pinfunction "PB12_P12") (pintype "bidirectional"))
      (node (ref "JP2") (pin "10") (pinfunction "10_10") (pintype "passive"))
    )
    (net (code "163") (name "/USBH_VBUS") (class "Default")
      (node (ref "IC1") (pin "P13") (pinfunction "PB13_P13") (pintype "bidirectional"))
      (node (ref "JP2") (pin "4") (pinfunction "4_4") (pintype "passive"))
    )
    (net (code "164") (name "AGND") (class "Default")
      (node (ref "C11") (pin "2") (pinfunction "2_2") (pintype "passive"))
      (node (ref "C12") (pin "2") (pinfunction "2_2") (pintype "passive"))
      (node (ref "C21") (pin "2") (pinfunction "2_2") (pintype "passive"))
      (node (ref "C24") (pin "2") (pinfunction "2_2") (pintype "passive"))
      (node (ref "C25") (pin "-") (pinfunction "-_-") (pintype "passive"))
      (node (ref "C28") (pin "-") (pinfunction "-_-") (pintype "passive"))
      (node (ref "C29") (pin "-") (pinfunction "-_-") (pintype "passive"))
      (node (ref "C30") (pin "-") (pinfunction "-_-") (pintype "passive"))
      (node (ref "C31") (pin "-") (pinfunction "-_-") (pintype "passive"))
      (node (ref "C32") (pin "2") (pinfunction "2_2") (pintype "passive"))
      (node (ref "C33") (pin "2") (pinfunction "2_2") (pintype "passive"))
      (node (ref "C34") (pin "2") (pinfunction "2_2") (pintype "passive"))
      (node (ref "C35") (pin "2") (pinfunction "2_2") (pintype "passive"))
      (node (ref "IC1") (pin "M1") (pinfunction "VSSA_M1") (pintype "bidirectional"))
      (node (ref "IC1") (pin "N1") (pinfunction "VREF-_N1") (pintype "bidirectional"))
      (node (ref "JP1") (pin "33") (pinfunction "33_33") (pintype "passive"))
      (node (ref "JP1") (pin "47") (pinfunction "47_47") (pintype "passive"))
      (node (ref "JP1") (pin "48") (pinfunction "48_48") (pintype "passive"))
      (node (ref "JP2") (pin "25") (pinfunction "25_25") (pintype "passive"))
      (node (ref "JP2") (pin "26") (pinfunction "26_26") (pintype "passive"))
      (node (ref "JP2") (pin "29") (pinfunction "29_29") (pintype "passive"))
      (node (ref "JP2") (pin "47") (pinfunction "47_47") (pintype "passive"))
      (node (ref "JP2") (pin "48") (pinfunction "48_48") (pintype "passive"))
      (node (ref "L1") (pin "1") (pinfunction "1_1") (pintype "passive"))
      (node (ref "U2") (pin "16") (pinfunction "AGNDDA1_16") (pintype "bidirectional"))
      (node (ref "U2") (pin "2") (pinfunction "AGNDAD2_2") (pintype "bidirectional"))
      (node (ref "U2") (pin "33") (pinfunction "AGNDDA2_33") (pintype "bidirectional"))
      (node (ref "U2") (pin "50") (pinfunction "AGNDAD1_50") (pintype "bidirectional"))
      (node (ref "U2") (pin "EP") (pinfunction "AGND_EP") (pintype "bidirectional"))
    )
    (net (code "165") (name "GND") (class "Default")
      (node (ref "C1") (pin "2") (pinfunction "2_2") (pintype "passive"))
      (node (ref "C10") (pin "2") (pinfunction "2_2") (pintype "passive"))
      (node (ref "C13") (pin "2") (pinfunction "2_2") (pintype "passive"))
      (node (ref "C14") (pin "2") (pinfunction "2_2") (pintype "passive"))
      (node (ref "C16") (pin "-") (pinfunction "-_-") (pintype "passive"))
      (node (ref "C18") (pin "-") (pinfunction "-_-") (pintype "passive"))
      (node (ref "C19") (pin "-") (pinfunction "-_-") (pintype "passive"))
      (node (ref "C2") (pin "2") (pinfunction "2_2") (pintype "passive"))
      (node (ref "C20") (pin "2") (pinfunction "2_2") (pintype "passive"))
      (node (ref "C22") (pin "2") (pinfunction "2_2") (pintype "passive"))
      (node (ref "C23") (pin "2") (pinfunction "2_2") (pintype "passive"))
      (node (ref "C26") (pin "2") (pinfunction "2_2") (pintype "passive"))
      (node (ref "C3") (pin "2") (pinfunction "2_2") (pintype "passive"))
      (node (ref "C36") (pin "2") (pinfunction "2_2") (pintype "passive"))
      (node (ref "C37") (pin "2") (pinfunction "2_2") (pintype "passive"))
      (node (ref "C38") (pin "1") (pinfunction "1_1") (pintype "passive"))
      (node (ref "C39") (pin "2") (pinfunction "2_2") (pintype "passive"))
      (node (ref "C4") (pin "2") (pinfunction "2_2") (pintype "passive"))
      (node (ref "C40") (pin "2") (pinfunction "2_2") (pintype "passive"))
      (node (ref "C5") (pin "2") (pinfunction "2_2") (pintype "passive"))
      (node (ref "C6") (pin "2") (pinfunction "2_2") (pintype "passive"))
      (node (ref "C7") (pin "2") (pinfunction "2_2") (pintype "passive"))
      (node (ref "C8") (pin "2") (pinfunction "2_2") (pintype "passive"))
      (node (ref "C9") (pin "2") (pinfunction "2_2") (pintype "passive"))
      (node (ref "C90") (pin "2") (pinfunction "2_2") (pintype "passive"))
      (node (ref "CN1") (pin "5") (pinfunction "GND_5") (pintype "bidirectional"))
      (node (ref "CN1") (pin "G") (pinfunction "SHIELD_G") (pintype "bidirectional"))
      (node (ref "CN1") (pin "G2") (pinfunction "SHIELD_G2") (pintype "bidirectional"))
      (node (ref "CN1") (pin "G3") (pinfunction "SHIELD_G3") (pintype "bidirectional"))
      (node (ref "CN1") (pin "G4") (pinfunction "SHIELD_G4") (pintype "bidirectional"))
      (node (ref "IC1") (pin "D5") (pinfunction "VSS_1_D5") (pintype "bidirectional"))
      (node (ref "IC1") (pin "D7") (pinfunction "VSS_2_D7") (pintype "bidirectional"))
      (node (ref "IC1") (pin "D8") (pinfunction "VSS_3_D8") (pintype "bidirectional"))
      (node (ref "IC1") (pin "D9") (pinfunction "VSS_4_D9") (pintype "bidirectional"))
      (node (ref "IC1") (pin "F10") (pinfunction "VSS_10_F10") (pintype "bidirectional"))
      (node (ref "IC1") (pin "F12") (pinfunction "VSS_11_F12") (pintype "bidirectional"))
      (node (ref "IC1") (pin "F2") (pinfunction "VSS_5_F2") (pintype "bidirectional"))
      (node (ref "IC1") (pin "F6") (pinfunction "VSS_6_F6") (pintype "bidirectional"))
      (node (ref "IC1") (pin "F7") (pinfunction "VSS_7_F7") (pintype "bidirectional"))
      (node (ref "IC1") (pin "F8") (pinfunction "VSS_8_F8") (pintype "bidirectional"))
      (node (ref "IC1") (pin "F9") (pinfunction "VSS_9_F9") (pintype "bidirectional"))
      (node (ref "IC1") (pin "G10") (pinfunction "VSS_17_G10") (pintype "bidirectional"))
      (node (ref "IC1") (pin "G12") (pinfunction "VSS_18_G12") (pintype "bidirectional"))
      (node (ref "IC1") (pin "G2") (pinfunction "VSS_12_G2") (pintype "bidirectional"))
      (node (ref "IC1") (pin "G6") (pinfunction "VSS_13_G6") (pintype "bidirectional"))
      (node (ref "IC1") (pin "G7") (pinfunction "VSS_14_G7") (pintype "bidirectional"))
      (node (ref "IC1") (pin "G8") (pinfunction "VSS_15_G8") (pintype "bidirectional"))
      (node (ref "IC1") (pin "G9") (pinfunction "VSS_16_G9") (pintype "bidirectional"))
      (node (ref "IC1") (pin "H10") (pinfunction "VSS_23_H10") (pintype "bidirectional"))
      (node (ref "IC1") (pin "H12") (pinfunction "VSS_24_H12") (pintype "bidirectional"))
      (node (ref "IC1") (pin "H6") (pinfunction "VSS_19_H6") (pintype "bidirectional"))
      (node (ref "IC1") (pin "H7") (pinfunction "VSS_20_H7") (pintype "bidirectional"))
      (node (ref "IC1") (pin "H8") (pinfunction "VSS_21_H8") (pintype "bidirectional"))
      (node (ref "IC1") (pin "H9") (pinfunction "VSS_22_H9") (pintype "bidirectional"))
      (node (ref "IC1") (pin "J10") (pinfunction "VSS_29_J10") (pintype "bidirectional"))
      (node (ref "IC1") (pin "J6") (pinfunction "VSS_25_J6") (pintype "bidirectional"))
      (node (ref "IC1") (pin "J7") (pinfunction "VSS_26_J7") (pintype "bidirectional"))
      (node (ref "IC1") (pin "J8") (pinfunction "VSS_27_J8") (pintype "bidirectional"))
      (node (ref "IC1") (pin "J9") (pinfunction "VSS_28_J9") (pintype "bidirectional"))
      (node (ref "IC1") (pin "K10") (pinfunction "VSS_34_K10") (pintype "bidirectional"))
      (node (ref "IC1") (pin "K6") (pinfunction "VSS_30_K6") (pintype "bidirectional"))
      (node (ref "IC1") (pin "K7") (pinfunction "VSS_31_K7") (pintype "bidirectional"))
      (node (ref "IC1") (pin "K8") (pinfunction "VSS_32_K8") (pintype "bidirectional"))
      (node (ref "IC1") (pin "K9") (pinfunction "VSS_33_K9") (pintype "bidirectional"))
      (node (ref "IC1") (pin "L4") (pinfunction "VSS_35_L4") (pintype "bidirectional"))
      (node (ref "IC1") (pin "M8") (pinfunction "VSS_36_M8") (pintype "bidirectional"))
      (node (ref "IC1") (pin "M9") (pinfunction "VSS_37_M9") (pintype "bidirectional"))
      (node (ref "IC2") (pin "A3") (pinfunction "VSS_1_A3") (pintype "bidirectional"))
      (node (ref "IC2") (pin "B3") (pinfunction "VSSQ_1_B3") (pintype "bidirectional"))
      (node (ref "IC2") (pin "B8") (pinfunction "VSSQ_2_B8") (pintype "bidirectional"))
      (node (ref "IC2") (pin "C1") (pinfunction "VSSQ_3_C1") (pintype "bidirectional"))
      (node (ref "IC2") (pin "D1") (pinfunction "VSSQ_4_D1") (pintype "bidirectional"))
      (node (ref "IC2") (pin "E9") (pinfunction "VSSQ_5_E9") (pintype "bidirectional"))
      (node (ref "IC2") (pin "F1") (pinfunction "VSS_2_F1") (pintype "bidirectional"))
      (node (ref "IC2") (pin "L3") (pinfunction "VSS_3_L3") (pintype "bidirectional"))
      (node (ref "IC2") (pin "L9") (pinfunction "VSSQ_6_L9") (pintype "bidirectional"))
      (node (ref "IC2") (pin "M1") (pinfunction "VSSQ_7_M1") (pintype "bidirectional"))
      (node (ref "IC2") (pin "N1") (pinfunction "VSSQ_8_N1") (pintype "bidirectional"))
      (node (ref "IC2") (pin "P3") (pinfunction "VSSQ_9_P3") (pintype "bidirectional"))
      (node (ref "IC2") (pin "P8") (pinfunction "VSSQ_10_P8") (pintype "bidirectional"))
      (node (ref "IC2") (pin "R3") (pinfunction "VSS_4_R3") (pintype "bidirectional"))
      (node (ref "IC9") (pin "4") (pinfunction "VSS_4") (pintype "bidirectional"))
      (node (ref "J1") (pin "3") (pinfunction "GND_3") (pintype "bidirectional"))
      (node (ref "J1") (pin "5") (pinfunction "GND_5") (pintype "bidirectional"))
      (node (ref "J1") (pin "7") (pinfunction "GND_7") (pintype "bidirectional"))
      (node (ref "J1") (pin "9") (pinfunction "GND_9") (pintype "bidirectional"))
      (node (ref "JP1") (pin "15") (pinfunction "15_15") (pintype "passive"))
      (node (ref "JP1") (pin "16") (pinfunction "16_16") (pintype "passive"))
      (node (ref "JP2") (pin "11") (pinfunction "11_11") (pintype "passive"))
      (node (ref "JP2") (pin "12") (pinfunction "12_12") (pintype "passive"))
      (node (ref "L1") (pin "2") (pinfunction "2_2") (pintype "passive"))
      (node (ref "R1") (pin "1") (pinfunction "1_1") (pintype "passive"))
      (node (ref "U2") (pin "11") (pinfunction "DGND_11") (pintype "bidirectional"))
      (node (ref "U2") (pin "47") (pinfunction "DGND_47") (pintype "bidirectional"))
      (node (ref "U3") (pin "1") (pinfunction "ADJ_1") (pintype "input"))
    )
    (net (code "166") (name "Net-(IC1-PH0-_OSC_IN)") (class "Default")
      (node (ref "C22") (pin "1") (pinfunction "1_1") (pintype "passive"))
      (node (ref "IC1") (pin "G1") (pinfunction "PH0-_OSC_IN_G1") (pintype "bidirectional"))
      (node (ref "Y1") (pin "2") (pinfunction "2_2") (pintype "passive"))
    )
    (net (code "167") (name "Net-(IC1-PH1-_OSC___OUT)") (class "Default")
      (node (ref "C23") (pin "1") (pinfunction "1_1") (pintype "passive"))
      (node (ref "IC1") (pin "H1") (pinfunction "PH1-_OSC___OUT_H1") (pintype "bidirectional"))
      (node (ref "Y1") (pin "1") (pinfunction "1_1") (pintype "passive"))
    )
    (net (code "168") (name "Net-(IC1-VCAP_1)") (class "Default")
      (node (ref "C13") (pin "1") (pinfunction "1_1") (pintype "passive"))
      (node (ref "IC1") (pin "F13") (pinfunction "VCAP_1_F13") (pintype "bidirectional"))
    )
    (net (code "169") (name "Net-(IC1-VCAP_2)") (class "Default")
      (node (ref "C14") (pin "1") (pinfunction "1_1") (pintype "passive"))
      (node (ref "IC1") (pin "M10") (pinfunction "VCAP_2_M10") (pintype "bidirectional"))
    )
    (net (code "170") (name "Net-(U2-VREFAD1)") (class "Default")
      (node (ref "C29") (pin "+") (pinfunction "+_+") (pintype "passive"))
      (node (ref "U2") (pin "59") (pinfunction "VREFAD1_59") (pintype "bidirectional"))
    )
    (net (code "171") (name "Net-(U2-VREFAD2)") (class "Default")
      (node (ref "C28") (pin "+") (pinfunction "+_+") (pintype "passive"))
      (node (ref "U2") (pin "60") (pinfunction "VREFAD2_60") (pintype "bidirectional"))
    )
    (net (code "172") (name "unconnected-(IC1-PB2-PadM6)") (class "Default")
      (node (ref "IC1") (pin "M6") (pinfunction "PB2_M6") (pintype "bidirectional"))
    )
    (net (code "173") (name "unconnected-(IC1-PB9-PadB4)") (class "Default")
      (node (ref "IC1") (pin "B4") (pinfunction "PB9_B4") (pintype "bidirectional"))
    )
    (net (code "174") (name "unconnected-(IC1-PD3-PadD11)") (class "Default")
      (node (ref "IC1") (pin "D11") (pinfunction "PD3_D11") (pintype "bidirectional"))
    )
    (net (code "175") (name "unconnected-(IC1-PD4-PadD10)") (class "Default")
      (node (ref "IC1") (pin "D10") (pinfunction "PD4_D10") (pintype "bidirectional"))
    )
    (net (code "176") (name "unconnected-(IC1-PD5-PadC11)") (class "Default")
      (node (ref "IC1") (pin "C11") (pinfunction "PD5_C11") (pintype "bidirectional"))
    )
    (net (code "177") (name "unconnected-(IC1-PD6-PadB11)") (class "Default")
      (node (ref "IC1") (pin "B11") (pinfunction "PD6_B11") (pintype "bidirectional"))
    )
    (net (code "178") (name "unconnected-(IC1-PD7-PadA11)") (class "Default")
      (node (ref "IC1") (pin "A11") (pinfunction "PD7_A11") (pintype "bidirectional"))
    )
    (net (code "179") (name "unconnected-(IC1-PD11-PadN14)") (class "Default")
      (node (ref "IC1") (pin "N14") (pinfunction "PD11_N14") (pintype "bidirectional"))
    )
    (net (code "180") (name "unconnected-(IC1-PG9-PadC10)") (class "Default")
      (node (ref "IC1") (pin "C10") (pinfunction "PG9_C10") (pintype "bidirectional"))
    )
    (net (code "181") (name "unconnected-(IC1-PH6-PadM11)") (class "Default")
      (node (ref "IC1") (pin "M11") (pinfunction "PH6_M11") (pintype "bidirectional"))
    )
    (net (code "182") (name "unconnected-(IC1-PH7-PadN12)") (class "Default")
      (node (ref "IC1") (pin "N12") (pinfunction "PH7_N12") (pintype "bidirectional"))
    )
    (net (code "183") (name "unconnected-(IC1-PI8-PadD2)") (class "Default")
      (node (ref "IC1") (pin "D2") (pinfunction "PI8_D2") (pintype "bidirectional"))
    )
    (net (code "184") (name "unconnected-(IC1-VBAT-PadC1)") (class "Default")
      (node (ref "IC1") (pin "C1") (pinfunction "VBAT_C1") (pintype "bidirectional"))
    )
    (net (code "185") (name "unconnected-(IC2-NC_1-PadE3)") (class "Default")
      (node (ref "IC2") (pin "E3") (pinfunction "NC_1_E3") (pintype "bidirectional"))
    )
    (net (code "186") (name "unconnected-(IC2-NC_2-PadE7)") (class "Default")
      (node (ref "IC2") (pin "E7") (pinfunction "NC_2_E7") (pintype "bidirectional"))
    )
    (net (code "187") (name "unconnected-(IC2-NC_3-PadH7)") (class "Default")
      (node (ref "IC2") (pin "H7") (pinfunction "NC_3_H7") (pintype "bidirectional"))
    )
    (net (code "188") (name "unconnected-(IC2-NC_4-PadK2)") (class "Default")
      (node (ref "IC2") (pin "K2") (pinfunction "NC_4_K2") (pintype "bidirectional"))
    )
    (net (code "189") (name "unconnected-(IC2-NC_5-PadK3)") (class "Default")
      (node (ref "IC2") (pin "K3") (pinfunction "NC_5_K3") (pintype "bidirectional"))
    )
    (net (code "190") (name "unconnected-(J1-NC{slash}TDI-Pad8)") (class "Default")
      (node (ref "J1") (pin "8") (pinfunction "NC/TDI_8") (pintype "bidirectional"))
    )
    (net (code "191") (name "unconnected-(U2-DIN2-Pad38)") (class "Default")
      (node (ref "U2") (pin "38") (pinfunction "DIN2_38") (pintype "bidirectional"))
    )
    (net (code "192") (name "unconnected-(U2-DIN3-Pad39)") (class "Default")
      (node (ref "U2") (pin "39") (pinfunction "DIN3_39") (pintype "bidirectional"))
    )
    (net (code "193") (name "unconnected-(U2-DIN4-Pad40)") (class "Default")
      (node (ref "U2") (pin "40") (pinfunction "DIN4_40") (pintype "bidirectional"))
    )
    (net (code "194") (name "unconnected-(U2-DOUT2-Pad9)") (class "Default")
      (node (ref "U2") (pin "9") (pinfunction "DOUT2_9") (pintype "bidirectional"))
    )
    (net (code "195") (name "unconnected-(U2-DOUT3-Pad10)") (class "Default")
      (node (ref "U2") (pin "10") (pinfunction "DOUT3_10") (pintype "bidirectional"))
    )
    (net (code "196") (name "unconnected-(U2-OVF-Pad5)") (class "Default")
      (node (ref "U2") (pin "5") (pinfunction "OVF_5") (pintype "bidirectional"))
    )
    (net (code "197") (name "unconnected-(U2-ZERO-Pad13)") (class "Default")
      (node (ref "U2") (pin "13") (pinfunction "ZERO_13") (pintype "bidirectional"))
    )
  )
)
